# Pirxboard.net
KiCad netlist of a schematic drawn in EAGLE
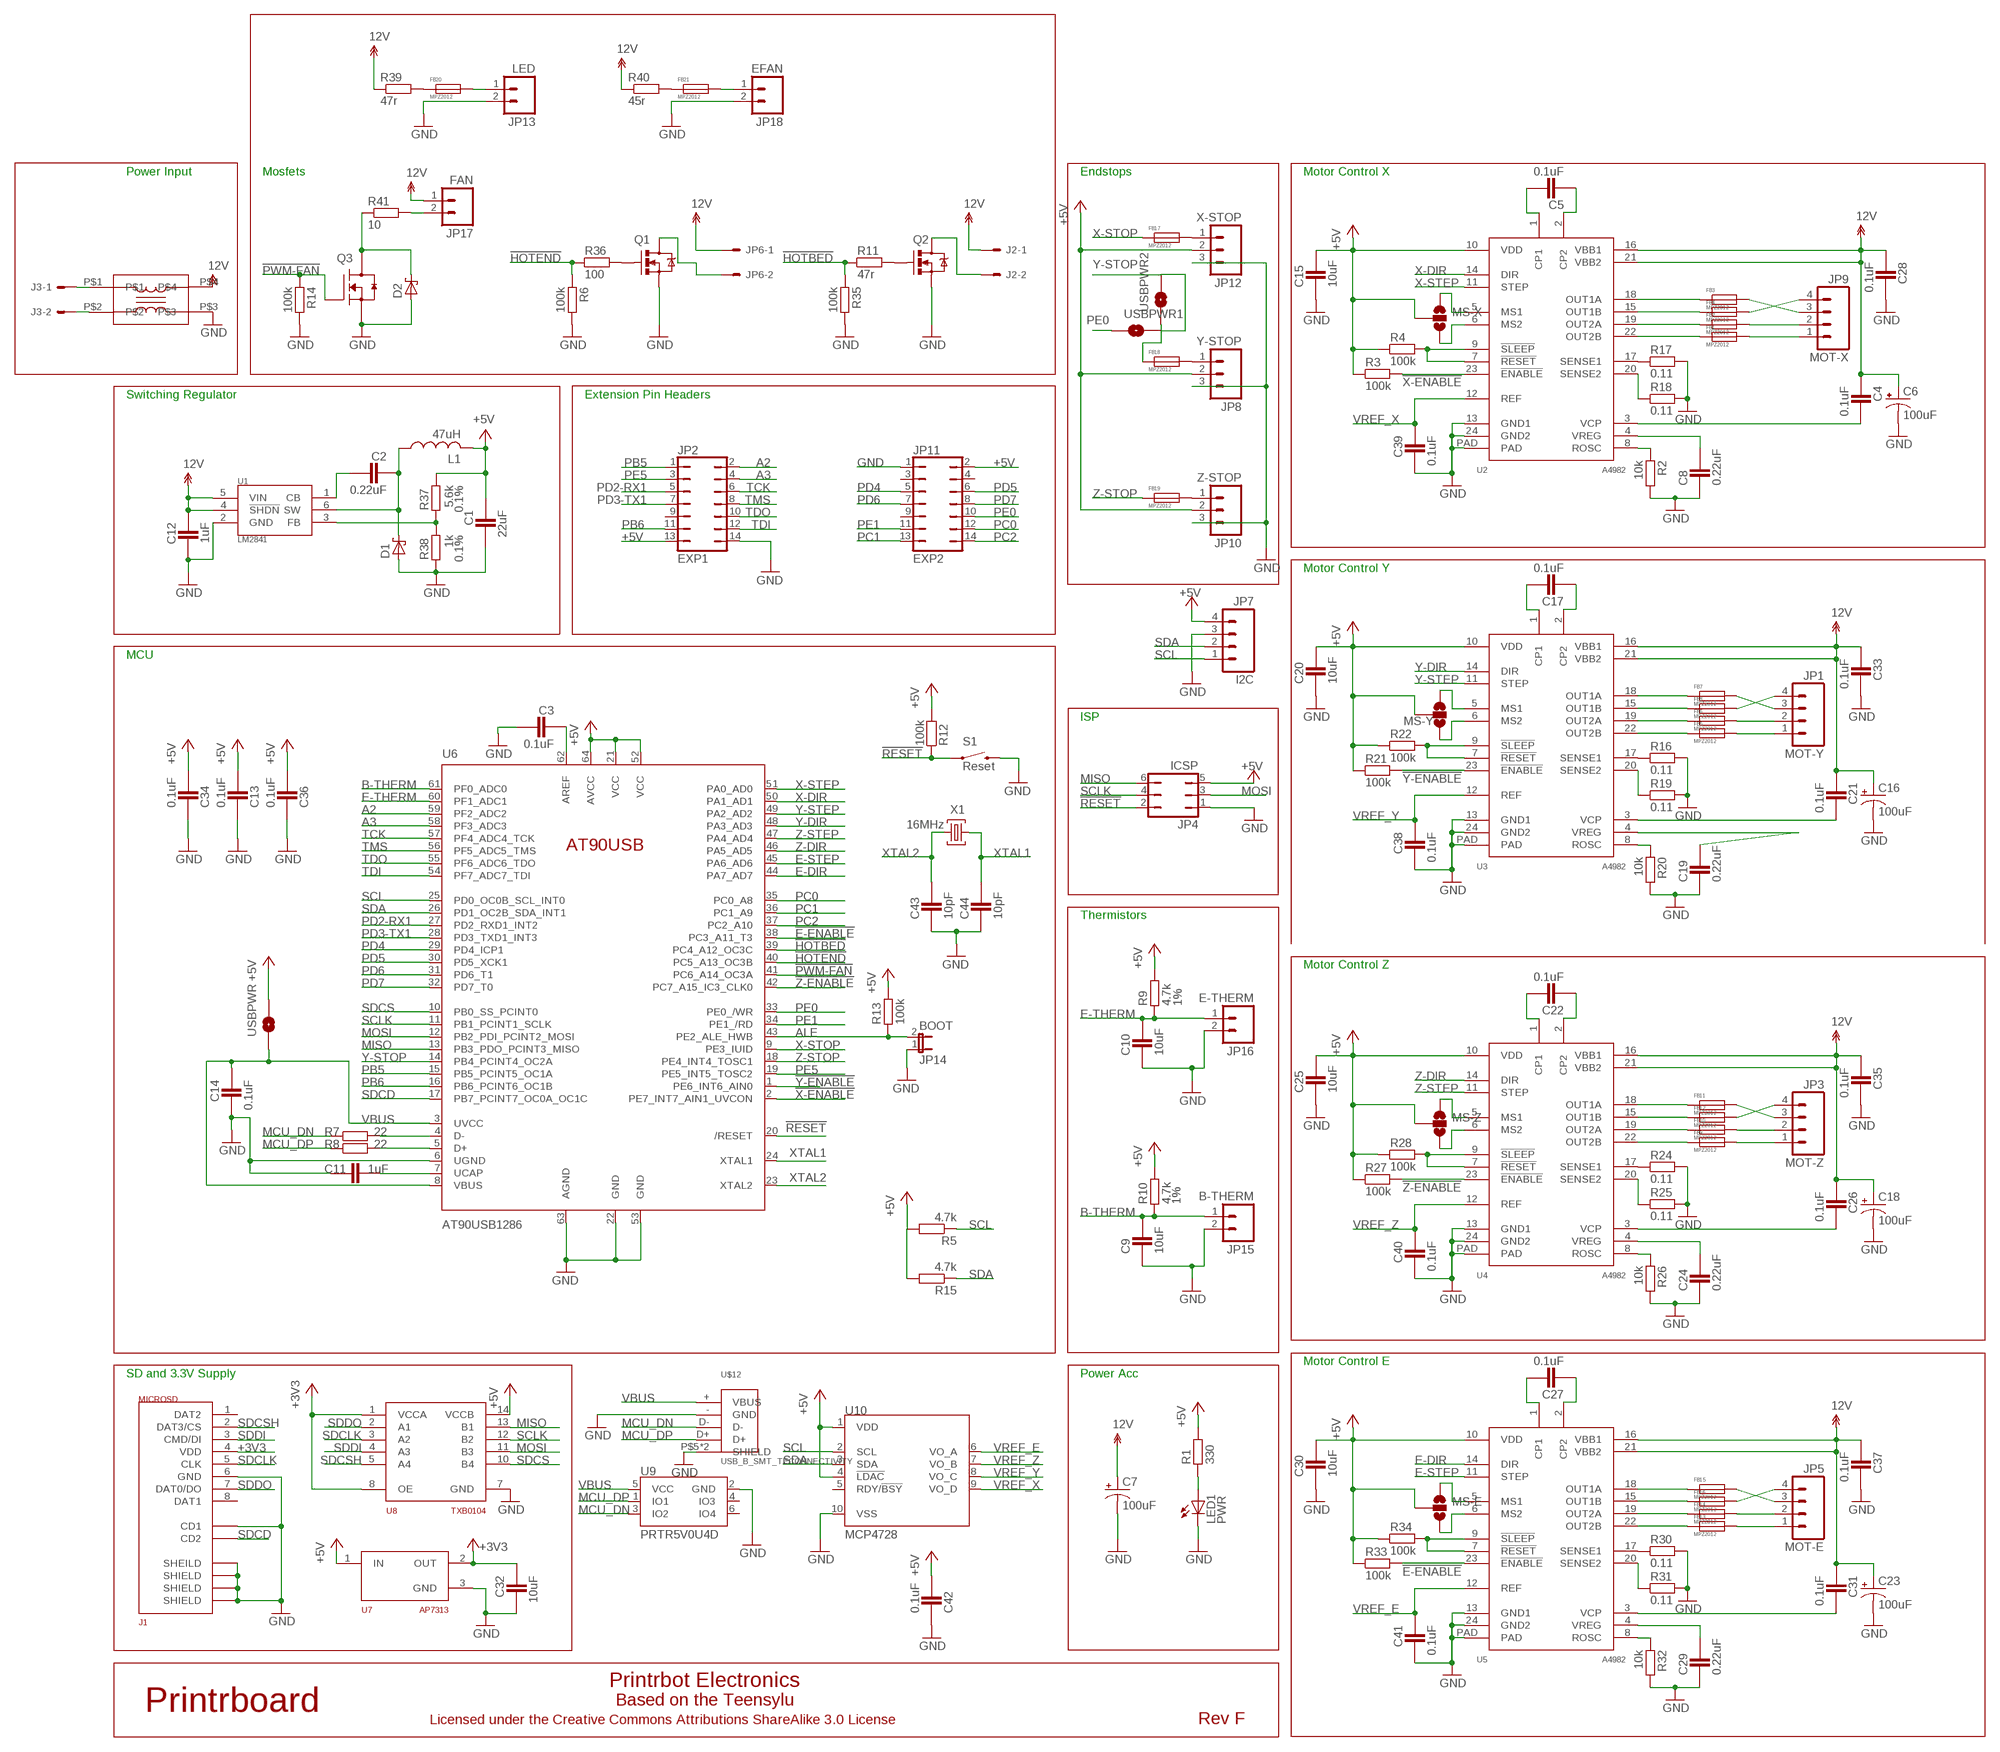
[diagram p0: schematic, sheet 1]

(export (version "E")
  (design (tool "Eeschema 10.0.6"))
  (components
    (comp (ref "C1")
      (value "22uF")
      (footprint "eagle-import:CAPC2012X145AN")
      (libsource (lib "eagle-import") (part "CAPACITOR_0805"))
    )
    (comp (ref "C2")
      (value "0.22uF")
      (footprint "eagle-import:CAPC2012X145AN")
      (libsource (lib "eagle-import") (part "CAPACITOR_0805"))
    )
    (comp (ref "C3")
      (value "0.1uF")
      (footprint "eagle-import:CAPC2012X145AN")
      (libsource (lib "eagle-import") (part "CAPACITOR_0805"))
    )
    (comp (ref "C4")
      (value "0.1uF")
      (footprint "eagle-import:CAPC2012X145AN")
      (libsource (lib "eagle-import") (part "CAPACITOR_0805"))
    )
    (comp (ref "C5")
      (value "0.1uF")
      (footprint "eagle-import:CAPC2012X145AN")
      (libsource (lib "eagle-import") (part "CAPACITOR_0805"))
    )
    (comp (ref "C6")
      (value "100uF")
      (footprint "eagle-import:PANASONIC_D")
      (libsource (lib "eagle-import") (part "CPOL-USD"))
    )
    (comp (ref "C7")
      (value "100uF")
      (footprint "eagle-import:PANASONIC_D")
      (libsource (lib "eagle-import") (part "CPOL-USD"))
    )
    (comp (ref "C8")
      (value "0.22uF")
      (footprint "eagle-import:CAPC2012X145AN")
      (libsource (lib "eagle-import") (part "CAPACITOR_0805"))
    )
    (comp (ref "C9")
      (value "10uF")
      (footprint "eagle-import:CAPC2012X145AN")
      (libsource (lib "eagle-import") (part "CAPACITOR_0805"))
    )
    (comp (ref "C10")
      (value "10uF")
      (footprint "eagle-import:CAPC2012X145AN")
      (libsource (lib "eagle-import") (part "CAPACITOR_0805"))
    )
    (comp (ref "C11")
      (value "1uF")
      (footprint "eagle-import:CAPC2012X145AN")
      (libsource (lib "eagle-import") (part "CAPACITOR_0805"))
    )
    (comp (ref "C12")
      (value "1uF")
      (footprint "eagle-import:CAPC2012X145AN")
      (libsource (lib "eagle-import") (part "CAPACITOR_0805"))
    )
    (comp (ref "C13")
      (value "0.1uF")
      (footprint "eagle-import:CAPC2012X145AN")
      (libsource (lib "eagle-import") (part "CAPACITOR_0805"))
    )
    (comp (ref "C14")
      (value "0.1uF")
      (footprint "eagle-import:CAPC2012X145AN")
      (libsource (lib "eagle-import") (part "CAPACITOR_0805"))
    )
    (comp (ref "C15")
      (value "10uF")
      (footprint "eagle-import:CAPC2012X145AN")
      (libsource (lib "eagle-import") (part "CAPACITOR_0805"))
    )
    (comp (ref "C16")
      (value "100uF")
      (footprint "eagle-import:PANASONIC_D")
      (libsource (lib "eagle-import") (part "CPOL-USD"))
    )
    (comp (ref "C17")
      (value "0.1uF")
      (footprint "eagle-import:CAPC2012X145AN")
      (libsource (lib "eagle-import") (part "CAPACITOR_0805"))
    )
    (comp (ref "C18")
      (value "100uF")
      (footprint "eagle-import:PANASONIC_D")
      (libsource (lib "eagle-import") (part "CPOL-USD"))
    )
    (comp (ref "C19")
      (value "0.22uF")
      (footprint "eagle-import:CAPC2012X145AN")
      (libsource (lib "eagle-import") (part "CAPACITOR_0805"))
    )
    (comp (ref "C20")
      (value "10uF")
      (footprint "eagle-import:CAPC2012X145AN")
      (libsource (lib "eagle-import") (part "CAPACITOR_0805"))
    )
    (comp (ref "C21")
      (value "0.1uF")
      (footprint "eagle-import:CAPC2012X145AN")
      (libsource (lib "eagle-import") (part "CAPACITOR_0805"))
    )
    (comp (ref "C22")
      (value "0.1uF")
      (footprint "eagle-import:CAPC2012X145AN")
      (libsource (lib "eagle-import") (part "CAPACITOR_0805"))
    )
    (comp (ref "C23")
      (value "100uF")
      (footprint "eagle-import:PANASONIC_D")
      (libsource (lib "eagle-import") (part "CPOL-USD"))
    )
    (comp (ref "C24")
      (value "0.22uF")
      (footprint "eagle-import:CAPC2012X145AN")
      (libsource (lib "eagle-import") (part "CAPACITOR_0805"))
    )
    (comp (ref "C25")
      (value "10uF")
      (footprint "eagle-import:CAPC2012X145AN")
      (libsource (lib "eagle-import") (part "CAPACITOR_0805"))
    )
    (comp (ref "C26")
      (value "0.1uF")
      (footprint "eagle-import:CAPC2012X145AN")
      (libsource (lib "eagle-import") (part "CAPACITOR_0805"))
    )
    (comp (ref "C27")
      (value "0.1uF")
      (footprint "eagle-import:CAPC2012X145AN")
      (libsource (lib "eagle-import") (part "CAPACITOR_0805"))
    )
    (comp (ref "C28")
      (value "0.1uF")
      (footprint "eagle-import:CAPC2012X145AN")
      (libsource (lib "eagle-import") (part "CAPACITOR_0805"))
    )
    (comp (ref "C29")
      (value "0.22uF")
      (footprint "eagle-import:CAPC2012X145AN")
      (libsource (lib "eagle-import") (part "CAPACITOR_0805"))
    )
    (comp (ref "C30")
      (value "10uF")
      (footprint "eagle-import:CAPC2012X145AN")
      (libsource (lib "eagle-import") (part "CAPACITOR_0805"))
    )
    (comp (ref "C31")
      (value "0.1uF")
      (footprint "eagle-import:CAPC2012X145AN")
      (libsource (lib "eagle-import") (part "CAPACITOR_0805"))
    )
    (comp (ref "C32")
      (value "10uF")
      (footprint "eagle-import:CAPC2012X145AN")
      (libsource (lib "eagle-import") (part "CAPACITOR_0805"))
    )
    (comp (ref "C33")
      (value "0.1uF")
      (footprint "eagle-import:CAPC2012X145AN")
      (libsource (lib "eagle-import") (part "CAPACITOR_0805"))
    )
    (comp (ref "C34")
      (value "0.1uF")
      (footprint "eagle-import:CAPC2012X145AN")
      (libsource (lib "eagle-import") (part "CAPACITOR_0805"))
    )
    (comp (ref "C35")
      (value "0.1uF")
      (footprint "eagle-import:CAPC2012X145AN")
      (libsource (lib "eagle-import") (part "CAPACITOR_0805"))
    )
    (comp (ref "C36")
      (value "0.1uF")
      (footprint "eagle-import:CAPC2012X145AN")
      (libsource (lib "eagle-import") (part "CAPACITOR_0805"))
    )
    (comp (ref "C37")
      (value "0.1uF")
      (footprint "eagle-import:CAPC2012X145AN")
      (libsource (lib "eagle-import") (part "CAPACITOR_0805"))
    )
    (comp (ref "C38")
      (value "0.1uF")
      (footprint "eagle-import:CAPC2012X145AN")
      (libsource (lib "eagle-import") (part "CAPACITOR_0805"))
    )
    (comp (ref "C39")
      (value "0.1uF")
      (footprint "eagle-import:CAPC2012X145AN")
      (libsource (lib "eagle-import") (part "CAPACITOR_0805"))
    )
    (comp (ref "C40")
      (value "0.1uF")
      (footprint "eagle-import:CAPC2012X145AN")
      (libsource (lib "eagle-import") (part "CAPACITOR_0805"))
    )
    (comp (ref "C41")
      (value "0.1uF")
      (footprint "eagle-import:CAPC2012X145AN")
      (libsource (lib "eagle-import") (part "CAPACITOR_0805"))
    )
    (comp (ref "C42")
      (value "0.1uF")
      (footprint "eagle-import:CAPC2012X145AN")
      (libsource (lib "eagle-import") (part "CAPACITOR_0805"))
    )
    (comp (ref "C43")
      (value "10pF")
      (footprint "eagle-import:CAPC2012X145AN")
      (libsource (lib "eagle-import") (part "CAPACITOR_0805"))
    )
    (comp (ref "C44")
      (value "10pF")
      (footprint "eagle-import:CAPC2012X145AN")
      (libsource (lib "eagle-import") (part "CAPACITOR_0805"))
    )
    (comp (ref "D1")
      (value "SCH-DIODESMA")
      (footprint "eagle-import:SMA")
      (libsource (lib "eagle-import") (part "SCH-DIODESMA"))
    )
    (comp (ref "D2")
      (value "SCH-DIODESMA")
      (footprint "eagle-import:SMA")
      (libsource (lib "eagle-import") (part "SCH-DIODESMA"))
    )
    (comp (ref "FB1")
      (value "MPZ2012")
      (footprint "eagle-import:FB2012")
      (libsource (lib "eagle-import") (part "MPZ2012"))
    )
    (comp (ref "FB2")
      (value "MPZ2012")
      (footprint "eagle-import:FB2012")
      (libsource (lib "eagle-import") (part "MPZ2012"))
    )
    (comp (ref "FB3")
      (value "MPZ2012")
      (footprint "eagle-import:FB2012")
      (libsource (lib "eagle-import") (part "MPZ2012"))
    )
    (comp (ref "FB4")
      (value "MPZ2012")
      (footprint "eagle-import:FB2012")
      (libsource (lib "eagle-import") (part "MPZ2012"))
    )
    (comp (ref "FB5")
      (value "MPZ2012")
      (footprint "eagle-import:FB2012")
      (libsource (lib "eagle-import") (part "MPZ2012"))
    )
    (comp (ref "FB6")
      (value "MPZ2012")
      (footprint "eagle-import:FB2012")
      (libsource (lib "eagle-import") (part "MPZ2012"))
    )
    (comp (ref "FB7")
      (value "MPZ2012")
      (footprint "eagle-import:FB2012")
      (libsource (lib "eagle-import") (part "MPZ2012"))
    )
    (comp (ref "FB8")
      (value "MPZ2012")
      (footprint "eagle-import:FB2012")
      (libsource (lib "eagle-import") (part "MPZ2012"))
    )
    (comp (ref "FB9")
      (value "MPZ2012")
      (footprint "eagle-import:FB2012")
      (libsource (lib "eagle-import") (part "MPZ2012"))
    )
    (comp (ref "FB10")
      (value "MPZ2012")
      (footprint "eagle-import:FB2012")
      (libsource (lib "eagle-import") (part "MPZ2012"))
    )
    (comp (ref "FB11")
      (value "MPZ2012")
      (footprint "eagle-import:FB2012")
      (libsource (lib "eagle-import") (part "MPZ2012"))
    )
    (comp (ref "FB12")
      (value "MPZ2012")
      (footprint "eagle-import:FB2012")
      (libsource (lib "eagle-import") (part "MPZ2012"))
    )
    (comp (ref "FB13")
      (value "MPZ2012")
      (footprint "eagle-import:FB2012")
      (libsource (lib "eagle-import") (part "MPZ2012"))
    )
    (comp (ref "FB14")
      (value "MPZ2012")
      (footprint "eagle-import:FB2012")
      (libsource (lib "eagle-import") (part "MPZ2012"))
    )
    (comp (ref "FB15")
      (value "MPZ2012")
      (footprint "eagle-import:FB2012")
      (libsource (lib "eagle-import") (part "MPZ2012"))
    )
    (comp (ref "FB16")
      (value "MPZ2012")
      (footprint "eagle-import:FB2012")
      (libsource (lib "eagle-import") (part "MPZ2012"))
    )
    (comp (ref "FB17")
      (value "MPZ2012")
      (footprint "eagle-import:FB2012")
      (libsource (lib "eagle-import") (part "MPZ2012"))
    )
    (comp (ref "FB18")
      (value "MPZ2012")
      (footprint "eagle-import:FB2012")
      (libsource (lib "eagle-import") (part "MPZ2012"))
    )
    (comp (ref "FB19")
      (value "MPZ2012")
      (footprint "eagle-import:FB2012")
      (libsource (lib "eagle-import") (part "MPZ2012"))
    )
    (comp (ref "FB20")
      (value "MPZ2012")
      (footprint "eagle-import:FB2012")
      (libsource (lib "eagle-import") (part "MPZ2012"))
    )
    (comp (ref "FB21")
      (value "MPZ2012")
      (footprint "eagle-import:FB2012")
      (libsource (lib "eagle-import") (part "MPZ2012"))
    )
    (comp (ref "J1")
      (value "MICROSD")
      (footprint "eagle-import:AMPHENOL-MICROSD")
      (libsource (lib "eagle-import") (part "MICROSD"))
    )
    (comp (ref "J2")
      (value "PHOENIX-2POS-5MM-SCREW")
      (footprint "eagle-import:PHOENIX-5MM-2POS")
      (libsource (lib "eagle-import") (part "PHOENIX-2POS-5MM-SCREW"))
    )
    (comp (ref "J3")
      (value "PHOENIX-2POS-5MM-SCREW")
      (footprint "eagle-import:PHOENIX-5MM-2POS")
      (libsource (lib "eagle-import") (part "PHOENIX-2POS-5MM-SCREW"))
    )
    (comp (ref "JP1")
      (value "MOT-Y")
      (footprint "eagle-import:MOLEX-1X4")
      (libsource (lib "eagle-import") (part "M04POLAR"))
    )
    (comp (ref "JP2")
      (value "EXP1")
      (footprint "eagle-import:JP7Q")
      (libsource (lib "eagle-import") (part "JP7Q"))
    )
    (comp (ref "JP3")
      (value "MOT-Z")
      (footprint "eagle-import:MOLEX-1X4")
      (libsource (lib "eagle-import") (part "M04POLAR"))
    )
    (comp (ref "JP4")
      (value "ICSP")
      (footprint "eagle-import:JP3Q")
      (libsource (lib "eagle-import") (part "JP3Q"))
    )
    (comp (ref "JP5")
      (value "MOT-E")
      (footprint "eagle-import:MOLEX-1X4")
      (libsource (lib "eagle-import") (part "M04POLAR"))
    )
    (comp (ref "JP6")
      (value "PHOENIX-2POS-5MM-SCREW")
      (footprint "eagle-import:PHOENIX-5MM-2POS")
      (libsource (lib "eagle-import") (part "PHOENIX-2POS-5MM-SCREW"))
    )
    (comp (ref "JP7")
      (value "I2C")
      (footprint "eagle-import:MOLEX-1X4")
      (libsource (lib "eagle-import") (part "M04POLAR"))
    )
    (comp (ref "JP8")
      (value "Y-STOP")
      (footprint "eagle-import:MOLEX-1X3")
      (libsource (lib "eagle-import") (part "M03POLAR"))
    )
    (comp (ref "JP9")
      (value "MOT-X")
      (footprint "eagle-import:MOLEX-1X4")
      (libsource (lib "eagle-import") (part "M04POLAR"))
    )
    (comp (ref "JP10")
      (value "Z-STOP")
      (footprint "eagle-import:MOLEX-1X3")
      (libsource (lib "eagle-import") (part "M03POLAR"))
    )
    (comp (ref "JP11")
      (value "EXP2")
      (footprint "eagle-import:JP7Q")
      (libsource (lib "eagle-import") (part "JP7Q"))
    )
    (comp (ref "JP12")
      (value "X-STOP")
      (footprint "eagle-import:MOLEX-1X3")
      (libsource (lib "eagle-import") (part "M03POLAR"))
    )
    (comp (ref "JP13")
      (value "LED")
      (footprint "eagle-import:1X02")
      (libsource (lib "eagle-import") (part "M02PTH"))
    )
    (comp (ref "JP14")
      (value "BOOT")
      (footprint "eagle-import:1X02")
      (libsource (lib "eagle-import") (part "JUMPER-2PTH"))
    )
    (comp (ref "JP15")
      (value "B-THERM")
      (footprint "eagle-import:1X02")
      (libsource (lib "eagle-import") (part "M02PTH"))
    )
    (comp (ref "JP16")
      (value "E-THERM")
      (footprint "eagle-import:1X02")
      (libsource (lib "eagle-import") (part "M02PTH"))
    )
    (comp (ref "JP17")
      (value "FAN")
      (footprint "eagle-import:1X02")
      (libsource (lib "eagle-import") (part "M02PTH"))
    )
    (comp (ref "JP18")
      (value "EFAN")
      (footprint "eagle-import:1X02")
      (libsource (lib "eagle-import") (part "M02PTH"))
    )
    (comp (ref "L1")
      (value "47uH")
      (footprint "eagle-import:SDR1006")
      (libsource (lib "eagle-import") (part "L-US"))
    )
    (comp (ref "LED1")
      (value "PWR")
      (footprint "eagle-import:CHIP-LED0805")
      (libsource (lib "eagle-import") (part "LEDCHIP-LED0805"))
    )
    (comp (ref "MS-E")
      (value "SOLDERJUMPER_2WAYCONNECTED")
      (footprint "eagle-import:SJ_3_CONNECTED")
      (libsource (lib "eagle-import") (part "SOLDERJUMPER_2WAYCONNECTED"))
    )
    (comp (ref "MS-X")
      (value "SOLDERJUMPER_2WAYCONNECTED")
      (footprint "eagle-import:SJ_3_CONNECTED")
      (libsource (lib "eagle-import") (part "SOLDERJUMPER_2WAYCONNECTED"))
    )
    (comp (ref "MS-Y")
      (value "SOLDERJUMPER_2WAYCONNECTED")
      (footprint "eagle-import:SJ_3_CONNECTED")
      (libsource (lib "eagle-import") (part "SOLDERJUMPER_2WAYCONNECTED"))
    )
    (comp (ref "MS-Z")
      (value "SOLDERJUMPER_2WAYCONNECTED")
      (footprint "eagle-import:SJ_3_CONNECTED")
      (libsource (lib "eagle-import") (part "SOLDERJUMPER_2WAYCONNECTED"))
    )
    (comp (ref "Q1")
      (value "RFP30N06LE")
      (footprint "eagle-import:TO220V")
      (libsource (lib "eagle-import") (part "MOSFET-NCHANNELPTH2"))
    )
    (comp (ref "Q2")
      (value "RFP30N06LE")
      (footprint "eagle-import:TO220V")
      (libsource (lib "eagle-import") (part "MOSFET-NCHANNELPTH2"))
    )
    (comp (ref "Q3")
      (value "RFP30N06LE")
      (footprint "eagle-import:SOT95P280X135-3N")
      (libsource (lib "eagle-import") (part "MOSFET-NCH_SOT-23"))
    )
    (comp (ref "R1")
      (value "330")
      (footprint "eagle-import:RESC2012X70N")
      (libsource (lib "eagle-import") (part "RESISTOR_0805"))
    )
    (comp (ref "R2")
      (value "10k")
      (footprint "eagle-import:RESC2012X70N")
      (libsource (lib "eagle-import") (part "RESISTOR_0805"))
    )
    (comp (ref "R3")
      (value "100k")
      (footprint "eagle-import:RESC2012X70N")
      (libsource (lib "eagle-import") (part "RESISTOR_0805"))
    )
    (comp (ref "R4")
      (value "100k")
      (footprint "eagle-import:RESC2012X70N")
      (libsource (lib "eagle-import") (part "RESISTOR_0805"))
    )
    (comp (ref "R5")
      (value "4.7k")
      (footprint "eagle-import:RESC2012X70N")
      (libsource (lib "eagle-import") (part "RESISTOR_0805"))
    )
    (comp (ref "R6")
      (value "100k")
      (footprint "eagle-import:RESC2012X70N")
      (libsource (lib "eagle-import") (part "RESISTOR_0805"))
    )
    (comp (ref "R7")
      (value "22")
      (footprint "eagle-import:RESC2012X70N")
      (libsource (lib "eagle-import") (part "RESISTOR_0805"))
    )
    (comp (ref "R8")
      (value "22")
      (footprint "eagle-import:RESC2012X70N")
      (libsource (lib "eagle-import") (part "RESISTOR_0805"))
    )
    (comp (ref "R9")
      (value "4.7k")
      (footprint "eagle-import:RESC2012X70N")
      (fields (field (name "TOLERANCE") "1%"))
      (libsource (lib "eagle-import") (part "RESISTOR_0805"))
    )
    (comp (ref "R10")
      (value "4.7k")
      (footprint "eagle-import:RESC2012X70N")
      (fields (field (name "TOLERANCE") "1%"))
      (libsource (lib "eagle-import") (part "RESISTOR_0805"))
    )
    (comp (ref "R11")
      (value "47r")
      (footprint "eagle-import:RESC2012X70N")
      (libsource (lib "eagle-import") (part "RESISTOR_0805"))
    )
    (comp (ref "R12")
      (value "100k")
      (footprint "eagle-import:RESC2012X70N")
      (libsource (lib "eagle-import") (part "RESISTOR_0805"))
    )
    (comp (ref "R13")
      (value "100k")
      (footprint "eagle-import:RESC2012X70N")
      (libsource (lib "eagle-import") (part "RESISTOR_0805"))
    )
    (comp (ref "R14")
      (value "100k")
      (footprint "eagle-import:RESC2012X70N")
      (libsource (lib "eagle-import") (part "RESISTOR_0805"))
    )
    (comp (ref "R15")
      (value "4.7k")
      (footprint "eagle-import:RESC2012X70N")
      (libsource (lib "eagle-import") (part "RESISTOR_0805"))
    )
    (comp (ref "R16")
      (value "0.11")
      (footprint "eagle-import:RESC2012X70N")
      (libsource (lib "eagle-import") (part "RESISTOR_0805"))
    )
    (comp (ref "R17")
      (value "0.11")
      (footprint "eagle-import:RESC2012X70N")
      (libsource (lib "eagle-import") (part "RESISTOR_0805"))
    )
    (comp (ref "R18")
      (value "0.11")
      (footprint "eagle-import:RESC2012X70N")
      (libsource (lib "eagle-import") (part "RESISTOR_0805"))
    )
    (comp (ref "R19")
      (value "0.11")
      (footprint "eagle-import:RESC2012X70N")
      (libsource (lib "eagle-import") (part "RESISTOR_0805"))
    )
    (comp (ref "R20")
      (value "10k")
      (footprint "eagle-import:RESC2012X70N")
      (libsource (lib "eagle-import") (part "RESISTOR_0805"))
    )
    (comp (ref "R21")
      (value "100k")
      (footprint "eagle-import:RESC2012X70N")
      (libsource (lib "eagle-import") (part "RESISTOR_0805"))
    )
    (comp (ref "R22")
      (value "100k")
      (footprint "eagle-import:RESC2012X70N")
      (libsource (lib "eagle-import") (part "RESISTOR_0805"))
    )
    (comp (ref "R24")
      (value "0.11")
      (footprint "eagle-import:RESC2012X70N")
      (libsource (lib "eagle-import") (part "RESISTOR_0805"))
    )
    (comp (ref "R25")
      (value "0.11")
      (footprint "eagle-import:RESC2012X70N")
      (libsource (lib "eagle-import") (part "RESISTOR_0805"))
    )
    (comp (ref "R26")
      (value "10k")
      (footprint "eagle-import:RESC2012X70N")
      (libsource (lib "eagle-import") (part "RESISTOR_0805"))
    )
    (comp (ref "R27")
      (value "100k")
      (footprint "eagle-import:RESC2012X70N")
      (libsource (lib "eagle-import") (part "RESISTOR_0805"))
    )
    (comp (ref "R28")
      (value "100k")
      (footprint "eagle-import:RESC2012X70N")
      (libsource (lib "eagle-import") (part "RESISTOR_0805"))
    )
    (comp (ref "R30")
      (value "0.11")
      (footprint "eagle-import:RESC2012X70N")
      (libsource (lib "eagle-import") (part "RESISTOR_0805"))
    )
    (comp (ref "R31")
      (value "0.11")
      (footprint "eagle-import:RESC2012X70N")
      (libsource (lib "eagle-import") (part "RESISTOR_0805"))
    )
    (comp (ref "R32")
      (value "10k")
      (footprint "eagle-import:RESC2012X70N")
      (libsource (lib "eagle-import") (part "RESISTOR_0805"))
    )
    (comp (ref "R33")
      (value "100k")
      (footprint "eagle-import:RESC2012X70N")
      (libsource (lib "eagle-import") (part "RESISTOR_0805"))
    )
    (comp (ref "R34")
      (value "100k")
      (footprint "eagle-import:RESC2012X70N")
      (libsource (lib "eagle-import") (part "RESISTOR_0805"))
    )
    (comp (ref "R35")
      (value "100k")
      (footprint "eagle-import:RESC2012X70N")
      (libsource (lib "eagle-import") (part "RESISTOR_0805"))
    )
    (comp (ref "R36")
      (value "100")
      (footprint "eagle-import:RESC2012X70N")
      (libsource (lib "eagle-import") (part "RESISTOR_0805"))
    )
    (comp (ref "R37")
      (value "5.6k")
      (footprint "eagle-import:RESC2012X70N")
      (fields (field (name "TOLERANCE") "0.1%"))
      (libsource (lib "eagle-import") (part "RESISTOR_0805"))
    )
    (comp (ref "R38")
      (value "1k")
      (footprint "eagle-import:RESC2012X70N")
      (fields (field (name "TOLERANCE") "0.1%"))
      (libsource (lib "eagle-import") (part "RESISTOR_0805"))
    )
    (comp (ref "R39")
      (value "47r")
      (footprint "eagle-import:R2512")
      (libsource (lib "eagle-import") (part "R-EU_R2512"))
    )
    (comp (ref "R40")
      (value "45r")
      (footprint "eagle-import:R2512")
      (libsource (lib "eagle-import") (part "R-EU_R2512"))
    )
    (comp (ref "R41")
      (value "10")
      (footprint "eagle-import:R2512")
      (libsource (lib "eagle-import") (part "R-EU_R2512"))
    )
    (comp (ref "S1")
      (value "Reset")
      (footprint "eagle-import:TACTILE_SWITCH_TALL")
      (libsource (lib "eagle-import") (part "SWITCH-MOMENTARY-2"))
    )
    (comp (ref "U$8")
      (value "ACM1513-551-2PLACM1513")
      (footprint "eagle-import:ACM1513")
      (libsource (lib "eagle-import") (part "ACM1513-551-2PLACM1513"))
    )
    (comp (ref "U$12")
      (value "USB_B_SMT_TECONNECTIVITY")
      (footprint "eagle-import:TECONECTIVITYUSBBSMT")
      (libsource (lib "eagle-import") (part "USB_B_SMT_TECONNECTIVITY"))
    )
    (comp (ref "U1")
      (value "LM2841")
      (footprint "eagle-import:TSOT6")
      (libsource (lib "eagle-import") (part "LM2841"))
    )
    (comp (ref "U2")
      (value "A4982")
      (footprint "eagle-import:TSSOP-24")
      (libsource (lib "eagle-import") (part "A4982"))
    )
    (comp (ref "U3")
      (value "A4982")
      (footprint "eagle-import:TSSOP-24")
      (libsource (lib "eagle-import") (part "A4982"))
    )
    (comp (ref "U4")
      (value "A4982")
      (footprint "eagle-import:TSSOP-24")
      (libsource (lib "eagle-import") (part "A4982"))
    )
    (comp (ref "U5")
      (value "A4982")
      (footprint "eagle-import:TSSOP-24")
      (libsource (lib "eagle-import") (part "A4982"))
    )
    (comp (ref "U6")
      (value "AT90USB1286")
      (footprint "eagle-import:TQFP64-2")
      (libsource (lib "eagle-import") (part "AT90USB"))
    )
    (comp (ref "U7")
      (value "AP7313")
      (footprint "eagle-import:SOT23C")
      (libsource (lib "eagle-import") (part "AP7313"))
    )
    (comp (ref "U8")
      (value "TXB0104")
      (footprint "eagle-import:TSSOP14")
      (libsource (lib "eagle-import") (part "TXB0104"))
    )
    (comp (ref "U9")
      (value "PRTR5V0U4D")
      (footprint "eagle-import:SOT23-6")
      (libsource (lib "eagle-import") (part "PRTR5V0U4D"))
    )
    (comp (ref "U10")
      (value "MCP4728")
      (footprint "eagle-import:MSOP10")
      (libsource (lib "eagle-import") (part "MCP4728"))
    )
    (comp (ref "USBPWR")
      (value "SOLDERJUMPERNO")
      (footprint "eagle-import:SJ_2S-NO")
      (libsource (lib "eagle-import") (part "SOLDERJUMPERNO"))
    )
    (comp (ref "USBPWR1")
      (value "SOLDERJUMPERNO")
      (footprint "eagle-import:SJ_2S-NO")
      (libsource (lib "eagle-import") (part "SOLDERJUMPERNO"))
    )
    (comp (ref "USBPWR2")
      (value "SOLDERJUMPERNO")
      (footprint "eagle-import:SJ_2S-NO")
      (libsource (lib "eagle-import") (part "SOLDERJUMPERNO"))
    )
    (comp (ref "X1")
      (value "16MHz")
      (footprint "eagle-import:NDK-XTAL")
      (libsource (lib "eagle-import") (part "XTAL"))
    )
  )
  (nets
    (net (code "1") (name "+3V3") (class "Default")
      (node (ref "C32") (pin "1") (pinfunction "1_1") (pintype "passive"))
      (node (ref "J1") (pin "4") (pinfunction "VDD_4") (pintype "power_in"))
      (node (ref "U7") (pin "2") (pinfunction "OUT_2") (pintype "power_in"))
      (node (ref "U8") (pin "1") (pinfunction "VCCA_1") (pintype "power_in"))
      (node (ref "U8") (pin "8") (pinfunction "OE_8") (pintype "input"))
    )
    (net (code "2") (name "+5V") (class "Default")
      (node (ref "C1") (pin "1") (pinfunction "1_1") (pintype "passive"))
      (node (ref "C13") (pin "2") (pinfunction "2_2") (pintype "passive"))
      (node (ref "C15") (pin "2") (pinfunction "2_2") (pintype "passive"))
      (node (ref "C20") (pin "2") (pinfunction "2_2") (pintype "passive"))
      (node (ref "C25") (pin "2") (pinfunction "2_2") (pintype "passive"))
      (node (ref "C30") (pin "2") (pinfunction "2_2") (pintype "passive"))
      (node (ref "C34") (pin "2") (pinfunction "2_2") (pintype "passive"))
      (node (ref "C36") (pin "2") (pinfunction "2_2") (pintype "passive"))
      (node (ref "C42") (pin "2") (pinfunction "2_2") (pintype "passive"))
      (node (ref "JP10") (pin "2") (pinfunction "2_2") (pintype "passive"))
      (node (ref "JP11") (pin "2") (pinfunction "2_2") (pintype "passive"))
      (node (ref "JP12") (pin "2") (pinfunction "2_2") (pintype "passive"))
      (node (ref "JP2") (pin "13") (pinfunction "13_13") (pintype "passive"))
      (node (ref "JP4") (pin "5") (pinfunction "5_5") (pintype "passive"))
      (node (ref "JP7") (pin "4") (pinfunction "4_4") (pintype "passive"))
      (node (ref "JP8") (pin "2") (pinfunction "2_2") (pintype "passive"))
      (node (ref "L1") (pin "P$2") (pinfunction "2_P$2") (pintype "passive"))
      (node (ref "MS-E") (pin "2") (pinfunction "2_2") (pintype "passive"))
      (node (ref "MS-X") (pin "2") (pinfunction "2_2") (pintype "passive"))
      (node (ref "MS-Y") (pin "2") (pinfunction "2_2") (pintype "passive"))
      (node (ref "MS-Z") (pin "2") (pinfunction "2_2") (pintype "passive"))
      (node (ref "R1") (pin "2") (pinfunction "2_2") (pintype "passive"))
      (node (ref "R10") (pin "2") (pinfunction "2_2") (pintype "passive"))
      (node (ref "R12") (pin "2") (pinfunction "2_2") (pintype "passive"))
      (node (ref "R13") (pin "2") (pinfunction "2_2") (pintype "passive"))
      (node (ref "R15") (pin "2") (pinfunction "2_2") (pintype "passive"))
      (node (ref "R21") (pin "1") (pinfunction "1_1") (pintype "passive"))
      (node (ref "R22") (pin "1") (pinfunction "1_1") (pintype "passive"))
      (node (ref "R27") (pin "1") (pinfunction "1_1") (pintype "passive"))
      (node (ref "R28") (pin "1") (pinfunction "1_1") (pintype "passive"))
      (node (ref "R3") (pin "1") (pinfunction "1_1") (pintype "passive"))
      (node (ref "R33") (pin "1") (pinfunction "1_1") (pintype "passive"))
      (node (ref "R34") (pin "1") (pinfunction "1_1") (pintype "passive"))
      (node (ref "R37") (pin "1") (pinfunction "1_1") (pintype "passive"))
      (node (ref "R4") (pin "1") (pinfunction "1_1") (pintype "passive"))
      (node (ref "R5") (pin "2") (pinfunction "2_2") (pintype "passive"))
      (node (ref "R9") (pin "2") (pinfunction "2_2") (pintype "passive"))
      (node (ref "U10") (pin "1") (pinfunction "VDD_1") (pintype "power_in"))
      (node (ref "U10") (pin "4") (pinfunction "~{LDAC}_4") (pintype "input"))
      (node (ref "U2") (pin "10") (pinfunction "VDD_10") (pintype "power_in"))
      (node (ref "U3") (pin "10") (pinfunction "VDD_10") (pintype "power_in"))
      (node (ref "U4") (pin "10") (pinfunction "VDD_10") (pintype "power_in"))
      (node (ref "U5") (pin "10") (pinfunction "VDD_10") (pintype "power_in"))
      (node (ref "U6") (pin "21") (pinfunction "VCC_21") (pintype "power_in"))
      (node (ref "U6") (pin "52") (pinfunction "VCC_52") (pintype "power_in"))
      (node (ref "U6") (pin "64") (pinfunction "AVCC_64") (pintype "power_in"))
      (node (ref "U7") (pin "1") (pinfunction "IN_1") (pintype "power_in"))
      (node (ref "U8") (pin "14") (pinfunction "VCCB_14") (pintype "power_in"))
      (node (ref "USBPWR") (pin "2") (pinfunction "2_2") (pintype "passive"))
    )
    (net (code "3") (name "/A2") (class "Default")
      (node (ref "JP2") (pin "2") (pinfunction "2_2") (pintype "passive"))
      (node (ref "U6") (pin "59") (pinfunction "PF2_ADC2_59") (pintype "bidirectional"))
    )
    (net (code "4") (name "/A3") (class "Default")
      (node (ref "JP2") (pin "4") (pinfunction "4_4") (pintype "passive"))
      (node (ref "U6") (pin "58") (pinfunction "PF3_ADC3_58") (pintype "bidirectional"))
    )
    (net (code "5") (name "/ALE") (class "Default")
      (node (ref "JP14") (pin "2") (pinfunction "2_2") (pintype "passive"))
      (node (ref "R13") (pin "1") (pinfunction "1_1") (pintype "passive"))
      (node (ref "U6") (pin "43") (pinfunction "PE2_ALE_HWB_43") (pintype "bidirectional"))
    )
    (net (code "6") (name "/B-THERM") (class "Default")
      (node (ref "C9") (pin "2") (pinfunction "2_2") (pintype "passive"))
      (node (ref "JP15") (pin "1") (pinfunction "1_1") (pintype "passive"))
      (node (ref "R10") (pin "1") (pinfunction "1_1") (pintype "passive"))
      (node (ref "U6") (pin "61") (pinfunction "PF0_ADC0_61") (pintype "bidirectional"))
    )
    (net (code "7") (name "/E-DIR") (class "Default")
      (node (ref "U5") (pin "14") (pinfunction "DIR_14") (pintype "input"))
      (node (ref "U6") (pin "44") (pinfunction "PA7_AD7_44") (pintype "bidirectional"))
    )
    (net (code "8") (name "/E-STEP") (class "Default")
      (node (ref "U5") (pin "11") (pinfunction "STEP_11") (pintype "input"))
      (node (ref "U6") (pin "45") (pinfunction "PA6_AD6_45") (pintype "bidirectional"))
    )
    (net (code "9") (name "/E-THERM") (class "Default")
      (node (ref "C10") (pin "2") (pinfunction "2_2") (pintype "passive"))
      (node (ref "JP16") (pin "1") (pinfunction "1_1") (pintype "passive"))
      (node (ref "R9") (pin "1") (pinfunction "1_1") (pintype "passive"))
      (node (ref "U6") (pin "60") (pinfunction "PF1_ADC1_60") (pintype "bidirectional"))
    )
    (net (code "10") (name "/MCU_DN") (class "Default")
      (node (ref "R7") (pin "1") (pinfunction "1_1") (pintype "passive"))
      (node (ref "U$12") (pin "D-") (pinfunction "D-_D-") (pintype "bidirectional"))
      (node (ref "U9") (pin "3") (pinfunction "IO2_3") (pintype "bidirectional"))
    )
    (net (code "11") (name "/MCU_DP") (class "Default")
      (node (ref "R8") (pin "1") (pinfunction "1_1") (pintype "passive"))
      (node (ref "U$12") (pin "D+") (pinfunction "D+_D+") (pintype "bidirectional"))
      (node (ref "U9") (pin "1") (pinfunction "IO1_1") (pintype "bidirectional"))
    )
    (net (code "12") (name "/MISO") (class "Default")
      (node (ref "JP4") (pin "6") (pinfunction "6_6") (pintype "passive"))
      (node (ref "U6") (pin "13") (pinfunction "PB3_PDO_PCINT3_MISO_13") (pintype "bidirectional"))
      (node (ref "U8") (pin "13") (pinfunction "B1_13") (pintype "bidirectional"))
    )
    (net (code "13") (name "/MOSI") (class "Default")
      (node (ref "JP4") (pin "3") (pinfunction "3_3") (pintype "passive"))
      (node (ref "U6") (pin "12") (pinfunction "PB2_PDI_PCINT2_MOSI_12") (pintype "bidirectional"))
      (node (ref "U8") (pin "11") (pinfunction "B3_11") (pintype "bidirectional"))
    )
    (net (code "14") (name "/PB5") (class "Default")
      (node (ref "JP2") (pin "1") (pinfunction "1_1") (pintype "passive"))
      (node (ref "U6") (pin "15") (pinfunction "PB5_PCINT5_OC1A_15") (pintype "bidirectional"))
    )
    (net (code "15") (name "/PB6") (class "Default")
      (node (ref "JP2") (pin "11") (pinfunction "11_11") (pintype "passive"))
      (node (ref "U6") (pin "16") (pinfunction "PB6_PCINT6_OC1B_16") (pintype "bidirectional"))
    )
    (net (code "16") (name "/PC0") (class "Default")
      (node (ref "JP11") (pin "12") (pinfunction "12_12") (pintype "passive"))
      (node (ref "U6") (pin "35") (pinfunction "PC0_A8_35") (pintype "bidirectional"))
    )
    (net (code "17") (name "/PC1") (class "Default")
      (node (ref "JP11") (pin "13") (pinfunction "13_13") (pintype "passive"))
      (node (ref "U6") (pin "36") (pinfunction "PC1_A9_36") (pintype "bidirectional"))
    )
    (net (code "18") (name "/PC2") (class "Default")
      (node (ref "JP11") (pin "14") (pinfunction "14_14") (pintype "passive"))
      (node (ref "U6") (pin "37") (pinfunction "PC2_A10_37") (pintype "bidirectional"))
    )
    (net (code "19") (name "/PD2-RX1") (class "Default")
      (node (ref "JP2") (pin "5") (pinfunction "5_5") (pintype "passive"))
      (node (ref "U6") (pin "27") (pinfunction "PD2_RXD1_INT2_27") (pintype "bidirectional"))
    )
    (net (code "20") (name "/PD3-TX1") (class "Default")
      (node (ref "JP2") (pin "7") (pinfunction "7_7") (pintype "passive"))
      (node (ref "U6") (pin "28") (pinfunction "PD3_TXD1_INT3_28") (pintype "bidirectional"))
    )
    (net (code "21") (name "/PD4") (class "Default")
      (node (ref "JP11") (pin "5") (pinfunction "5_5") (pintype "passive"))
      (node (ref "U6") (pin "29") (pinfunction "PD4_ICP1_29") (pintype "bidirectional"))
    )
    (net (code "22") (name "/PD5") (class "Default")
      (node (ref "JP11") (pin "6") (pinfunction "6_6") (pintype "passive"))
      (node (ref "U6") (pin "30") (pinfunction "PD5_XCK1_30") (pintype "bidirectional"))
    )
    (net (code "23") (name "/PD6") (class "Default")
      (node (ref "JP11") (pin "7") (pinfunction "7_7") (pintype "passive"))
      (node (ref "U6") (pin "31") (pinfunction "PD6_T1_31") (pintype "bidirectional"))
    )
    (net (code "24") (name "/PD7") (class "Default")
      (node (ref "JP11") (pin "8") (pinfunction "8_8") (pintype "passive"))
      (node (ref "U6") (pin "32") (pinfunction "PD7_T0_32") (pintype "bidirectional"))
    )
    (net (code "25") (name "/PE0") (class "Default")
      (node (ref "JP11") (pin "10") (pinfunction "10_10") (pintype "passive"))
      (node (ref "U6") (pin "33") (pinfunction "PE0_/WR_33") (pintype "bidirectional"))
      (node (ref "USBPWR1") (pin "1") (pinfunction "1_1") (pintype "passive"))
    )
    (net (code "26") (name "/PE1") (class "Default")
      (node (ref "JP11") (pin "11") (pinfunction "11_11") (pintype "passive"))
      (node (ref "U6") (pin "34") (pinfunction "PE1_/RD_34") (pintype "bidirectional"))
    )
    (net (code "27") (name "/PE5") (class "Default")
      (node (ref "JP2") (pin "3") (pinfunction "3_3") (pintype "passive"))
      (node (ref "U6") (pin "19") (pinfunction "PE5_INT5_TOSC2_19") (pintype "bidirectional"))
    )
    (net (code "28") (name "/SCL") (class "Default")
      (node (ref "JP7") (pin "1") (pinfunction "1_1") (pintype "passive"))
      (node (ref "R5") (pin "1") (pinfunction "1_1") (pintype "passive"))
      (node (ref "U10") (pin "2") (pinfunction "SCL_2") (pintype "input"))
      (node (ref "U6") (pin "25") (pinfunction "PD0_OC0B_SCL_INT0_25") (pintype "bidirectional"))
    )
    (net (code "29") (name "/SCLK") (class "Default")
      (node (ref "JP4") (pin "4") (pinfunction "4_4") (pintype "passive"))
      (node (ref "U6") (pin "11") (pinfunction "PB1_PCINT1_SCLK_11") (pintype "bidirectional"))
      (node (ref "U8") (pin "12") (pinfunction "B2_12") (pintype "bidirectional"))
    )
    (net (code "30") (name "/SDA") (class "Default")
      (node (ref "JP7") (pin "2") (pinfunction "2_2") (pintype "passive"))
      (node (ref "R15") (pin "1") (pinfunction "1_1") (pintype "passive"))
      (node (ref "U10") (pin "3") (pinfunction "SDA_3") (pintype "bidirectional"))
      (node (ref "U6") (pin "26") (pinfunction "PD1_OC2B_SDA_INT1_26") (pintype "bidirectional"))
    )
    (net (code "31") (name "/SDCD") (class "Default")
      (node (ref "J1") (pin "CD2") (pinfunction "CD2_CD2") (pintype "bidirectional"))
      (node (ref "U6") (pin "17") (pinfunction "PB7_PCINT7_OC0A_OC1C_17") (pintype "bidirectional"))
    )
    (net (code "32") (name "/SDCLK") (class "Default")
      (node (ref "J1") (pin "5") (pinfunction "CLK_5") (pintype "input"))
      (node (ref "U8") (pin "3") (pinfunction "A2_3") (pintype "bidirectional"))
    )
    (net (code "33") (name "/SDCS") (class "Default")
      (node (ref "U6") (pin "10") (pinfunction "PB0_SS_PCINT0_10") (pintype "bidirectional"))
      (node (ref "U8") (pin "10") (pinfunction "B4_10") (pintype "bidirectional"))
    )
    (net (code "34") (name "/SDCSH") (class "Default")
      (node (ref "J1") (pin "2") (pinfunction "DAT3/CS_2") (pintype "bidirectional"))
      (node (ref "U8") (pin "5") (pinfunction "A4_5") (pintype "bidirectional"))
    )
    (net (code "35") (name "/SDDI") (class "Default")
      (node (ref "J1") (pin "3") (pinfunction "CMD/DI_3") (pintype "input"))
      (node (ref "U8") (pin "4") (pinfunction "A3_4") (pintype "bidirectional"))
    )
    (net (code "36") (name "/SDDO") (class "Default")
      (node (ref "J1") (pin "7") (pinfunction "DAT0/DO_7") (pintype "bidirectional"))
      (node (ref "U8") (pin "2") (pinfunction "A1_2") (pintype "bidirectional"))
    )
    (net (code "37") (name "/TCK") (class "Default")
      (node (ref "JP2") (pin "6") (pinfunction "6_6") (pintype "passive"))
      (node (ref "U6") (pin "57") (pinfunction "PF4_ADC4_TCK_57") (pintype "bidirectional"))
    )
    (net (code "38") (name "/TDI") (class "Default")
      (node (ref "JP2") (pin "12") (pinfunction "12_12") (pintype "passive"))
      (node (ref "U6") (pin "54") (pinfunction "PF7_ADC7_TDI_54") (pintype "bidirectional"))
    )
    (net (code "39") (name "/TDO") (class "Default")
      (node (ref "JP2") (pin "10") (pinfunction "10_10") (pintype "passive"))
      (node (ref "U6") (pin "55") (pinfunction "PF6_ADC6_TDO_55") (pintype "bidirectional"))
    )
    (net (code "40") (name "/TMS") (class "Default")
      (node (ref "JP2") (pin "8") (pinfunction "8_8") (pintype "passive"))
      (node (ref "U6") (pin "56") (pinfunction "PF5_ADC5_TMS_56") (pintype "bidirectional"))
    )
    (net (code "41") (name "/VBUS") (class "Default")
      (node (ref "C14") (pin "1") (pinfunction "1_1") (pintype "passive"))
      (node (ref "U$12") (pin "+") (pinfunction "VBUS_+") (pintype "bidirectional"))
      (node (ref "U6") (pin "3") (pinfunction "UVCC_3") (pintype "power_in"))
      (node (ref "U6") (pin "8") (pinfunction "VBUS_8") (pintype "bidirectional"))
      (node (ref "U9") (pin "5") (pinfunction "VCC_5") (pintype "power_in"))
      (node (ref "USBPWR") (pin "1") (pinfunction "1_1") (pintype "passive"))
    )
    (net (code "42") (name "/VREF_E") (class "Default")
      (node (ref "C41") (pin "1") (pinfunction "1_1") (pintype "passive"))
      (node (ref "U10") (pin "6") (pinfunction "VO_A_6") (pintype "output"))
      (node (ref "U5") (pin "12") (pinfunction "REF_12") (pintype "input"))
    )
    (net (code "43") (name "/VREF_X") (class "Default")
      (node (ref "C39") (pin "1") (pinfunction "1_1") (pintype "passive"))
      (node (ref "U10") (pin "9") (pinfunction "VO_D_9") (pintype "output"))
      (node (ref "U2") (pin "12") (pinfunction "REF_12") (pintype "input"))
    )
    (net (code "44") (name "/VREF_Y") (class "Default")
      (node (ref "C38") (pin "1") (pinfunction "1_1") (pintype "passive"))
      (node (ref "U10") (pin "8") (pinfunction "VO_C_8") (pintype "output"))
      (node (ref "U3") (pin "12") (pinfunction "REF_12") (pintype "input"))
    )
    (net (code "45") (name "/VREF_Z") (class "Default")
      (node (ref "C40") (pin "1") (pinfunction "1_1") (pintype "passive"))
      (node (ref "U10") (pin "7") (pinfunction "VO_B_7") (pintype "output"))
      (node (ref "U4") (pin "12") (pinfunction "REF_12") (pintype "input"))
    )
    (net (code "46") (name "/X-DIR") (class "Default")
      (node (ref "U2") (pin "14") (pinfunction "DIR_14") (pintype "input"))
      (node (ref "U6") (pin "50") (pinfunction "PA1_AD1_50") (pintype "bidirectional"))
    )
    (net (code "47") (name "/X-STEP") (class "Default")
      (node (ref "U2") (pin "11") (pinfunction "STEP_11") (pintype "input"))
      (node (ref "U6") (pin "51") (pinfunction "PA0_AD0_51") (pintype "bidirectional"))
    )
    (net (code "48") (name "/X-STOP") (class "Default")
      (node (ref "FB17") (pin "P$1") (pinfunction "1_P$1") (pintype "passive"))
      (node (ref "U6") (pin "9") (pinfunction "PE3_IUID_9") (pintype "bidirectional"))
    )
    (net (code "49") (name "/XTAL1") (class "Default")
      (node (ref "C44") (pin "2") (pinfunction "2_2") (pintype "passive"))
      (node (ref "U6") (pin "24") (pinfunction "XTAL1_24") (pintype "passive"))
      (node (ref "X1") (pin "P$1") (pinfunction "1_P$1") (pintype "passive"))
    )
    (net (code "50") (name "/XTAL2") (class "Default")
      (node (ref "C43") (pin "2") (pinfunction "2_2") (pintype "passive"))
      (node (ref "U6") (pin "23") (pinfunction "XTAL2_23") (pintype "passive"))
      (node (ref "X1") (pin "P$2") (pinfunction "2_P$2") (pintype "passive"))
    )
    (net (code "51") (name "/Y-DIR") (class "Default")
      (node (ref "U3") (pin "14") (pinfunction "DIR_14") (pintype "input"))
      (node (ref "U6") (pin "48") (pinfunction "PA3_AD3_48") (pintype "bidirectional"))
    )
    (net (code "52") (name "/Y-STEP") (class "Default")
      (node (ref "U3") (pin "11") (pinfunction "STEP_11") (pintype "input"))
      (node (ref "U6") (pin "49") (pinfunction "PA2_AD2_49") (pintype "bidirectional"))
    )
    (net (code "53") (name "/Y-STOP") (class "Default")
      (node (ref "FB18") (pin "P$1") (pinfunction "1_P$1") (pintype "passive"))
      (node (ref "U6") (pin "14") (pinfunction "PB4_PCINT4_OC2A_14") (pintype "bidirectional"))
      (node (ref "USBPWR1") (pin "2") (pinfunction "2_2") (pintype "passive"))
      (node (ref "USBPWR2") (pin "1") (pinfunction "1_1") (pintype "passive"))
      (node (ref "USBPWR2") (pin "2") (pinfunction "2_2") (pintype "passive"))
    )
    (net (code "54") (name "/Z-DIR") (class "Default")
      (node (ref "U4") (pin "14") (pinfunction "DIR_14") (pintype "input"))
      (node (ref "U6") (pin "46") (pinfunction "PA5_AD5_46") (pintype "bidirectional"))
    )
    (net (code "55") (name "/Z-STEP") (class "Default")
      (node (ref "U4") (pin "11") (pinfunction "STEP_11") (pintype "input"))
      (node (ref "U6") (pin "47") (pinfunction "PA4_AD4_47") (pintype "bidirectional"))
    )
    (net (code "56") (name "/Z-STOP") (class "Default")
      (node (ref "FB19") (pin "P$1") (pinfunction "1_P$1") (pintype "passive"))
      (node (ref "U6") (pin "18") (pinfunction "PE4_INT4_TOSC1_18") (pintype "bidirectional"))
    )
    (net (code "57") (name "/~{E-ENABLE}") (class "Default")
      (node (ref "R33") (pin "2") (pinfunction "2_2") (pintype "passive"))
      (node (ref "U5") (pin "23") (pinfunction "~{ENABLE}_23") (pintype "input"))
      (node (ref "U6") (pin "38") (pinfunction "PC3_A11_T3_38") (pintype "bidirectional"))
    )
    (net (code "58") (name "/~{HOTBED}") (class "Default")
      (node (ref "R11") (pin "1") (pinfunction "1_1") (pintype "passive"))
      (node (ref "R35") (pin "1") (pinfunction "1_1") (pintype "passive"))
      (node (ref "U6") (pin "39") (pinfunction "PC4_A12_OC3C_39") (pintype "bidirectional"))
    )
    (net (code "59") (name "/~{HOTEND}") (class "Default")
      (node (ref "R36") (pin "1") (pinfunction "1_1") (pintype "passive"))
      (node (ref "R6") (pin "1") (pinfunction "1_1") (pintype "passive"))
      (node (ref "U6") (pin "40") (pinfunction "PC5_A13_OC3B_40") (pintype "bidirectional"))
    )
    (net (code "60") (name "/~{PWM-FAN}") (class "Default")
      (node (ref "Q3") (pin "1") (pinfunction "G_1") (pintype "passive"))
      (node (ref "R14") (pin "1") (pinfunction "1_1") (pintype "passive"))
      (node (ref "U6") (pin "41") (pinfunction "PC6_A14_OC3A_41") (pintype "bidirectional"))
    )
    (net (code "61") (name "/~{RESET}") (class "Default")
      (node (ref "JP4") (pin "2") (pinfunction "2_2") (pintype "passive"))
      (node (ref "R12") (pin "1") (pinfunction "1_1") (pintype "passive"))
      (node (ref "S1") (pin "A2") (pinfunction "1_A2") (pintype "passive"))
      (node (ref "U6") (pin "20") (pinfunction "/RESET_20") (pintype "bidirectional"))
    )
    (net (code "62") (name "/~{X-ENABLE}") (class "Default")
      (node (ref "R3") (pin "2") (pinfunction "2_2") (pintype "passive"))
      (node (ref "U2") (pin "23") (pinfunction "~{ENABLE}_23") (pintype "input"))
      (node (ref "U6") (pin "2") (pinfunction "PE7_INT7_AIN1_UVCON_2") (pintype "bidirectional"))
    )
    (net (code "63") (name "/~{Y-ENABLE}") (class "Default")
      (node (ref "R21") (pin "2") (pinfunction "2_2") (pintype "passive"))
      (node (ref "U3") (pin "23") (pinfunction "~{ENABLE}_23") (pintype "input"))
      (node (ref "U6") (pin "1") (pinfunction "PE6_INT6_AIN0_1") (pintype "bidirectional"))
    )
    (net (code "64") (name "/~{Z-ENABLE}") (class "Default")
      (node (ref "R27") (pin "2") (pinfunction "2_2") (pintype "passive"))
      (node (ref "U4") (pin "23") (pinfunction "~{ENABLE}_23") (pintype "input"))
      (node (ref "U6") (pin "42") (pinfunction "PC7_A15_IC3_CLK0_42") (pintype "bidirectional"))
    )
    (net (code "65") (name "12V") (class "Default")
      (node (ref "C12") (pin "1") (pinfunction "1_1") (pintype "passive"))
      (node (ref "C16") (pin "+") (pinfunction "+_+") (pintype "passive"))
      (node (ref "C18") (pin "+") (pinfunction "+_+") (pintype "passive"))
      (node (ref "C21") (pin "1") (pinfunction "1_1") (pintype "passive"))
      (node (ref "C23") (pin "+") (pinfunction "+_+") (pintype "passive"))
      (node (ref "C26") (pin "1") (pinfunction "1_1") (pintype "passive"))
      (node (ref "C28") (pin "1") (pinfunction "1_1") (pintype "passive"))
      (node (ref "C31") (pin "1") (pinfunction "1_1") (pintype "passive"))
      (node (ref "C33") (pin "1") (pinfunction "1_1") (pintype "passive"))
      (node (ref "C35") (pin "1") (pinfunction "1_1") (pintype "passive"))
      (node (ref "C37") (pin "1") (pinfunction "1_1") (pintype "passive"))
      (node (ref "C4") (pin "1") (pinfunction "1_1") (pintype "passive"))
      (node (ref "C6") (pin "+") (pinfunction "+_+") (pintype "passive"))
      (node (ref "C7") (pin "+") (pinfunction "+_+") (pintype "passive"))
      (node (ref "J2") (pin "P$1") (pinfunction "S_P$1") (pintype "passive"))
      (node (ref "JP17") (pin "1") (pinfunction "1_1") (pintype "passive"))
      (node (ref "JP6") (pin "P$1") (pinfunction "S_P$1") (pintype "passive"))
      (node (ref "R39") (pin "1") (pinfunction "1_1") (pintype "passive"))
      (node (ref "R40") (pin "1") (pinfunction "1_1") (pintype "passive"))
      (node (ref "U$8") (pin "P$4") (pinfunction "P$4_P$4") (pintype "bidirectional"))
      (node (ref "U1") (pin "4") (pinfunction "~{SHDN}_4") (pintype "input"))
      (node (ref "U1") (pin "5") (pinfunction "VIN_5") (pintype "power_in"))
      (node (ref "U2") (pin "16") (pinfunction "VBB1_16") (pintype "power_in"))
      (node (ref "U2") (pin "21") (pinfunction "VBB2_21") (pintype "power_in"))
      (node (ref "U3") (pin "16") (pinfunction "VBB1_16") (pintype "power_in"))
      (node (ref "U3") (pin "21") (pinfunction "VBB2_21") (pintype "power_in"))
      (node (ref "U4") (pin "16") (pinfunction "VBB1_16") (pintype "power_in"))
      (node (ref "U4") (pin "21") (pinfunction "VBB2_21") (pintype "power_in"))
      (node (ref "U5") (pin "16") (pinfunction "VBB1_16") (pintype "power_in"))
      (node (ref "U5") (pin "21") (pinfunction "VBB2_21") (pintype "power_in"))
    )
    (net (code "66") (name "GND") (class "Default")
      (node (ref "C1") (pin "2") (pinfunction "2_2") (pintype "passive"))
      (node (ref "C10") (pin "1") (pinfunction "1_1") (pintype "passive"))
      (node (ref "C11") (pin "1") (pinfunction "1_1") (pintype "passive"))
      (node (ref "C12") (pin "2") (pinfunction "2_2") (pintype "passive"))
      (node (ref "C13") (pin "1") (pinfunction "1_1") (pintype "passive"))
      (node (ref "C14") (pin "2") (pinfunction "2_2") (pintype "passive"))
      (node (ref "C15") (pin "1") (pinfunction "1_1") (pintype "passive"))
      (node (ref "C16") (pin "-") (pinfunction "-_-") (pintype "passive"))
      (node (ref "C18") (pin "-") (pinfunction "-_-") (pintype "passive"))
      (node (ref "C19") (pin "1") (pinfunction "1_1") (pintype "passive"))
      (node (ref "C20") (pin "1") (pinfunction "1_1") (pintype "passive"))
      (node (ref "C23") (pin "-") (pinfunction "-_-") (pintype "passive"))
      (node (ref "C24") (pin "1") (pinfunction "1_1") (pintype "passive"))
      (node (ref "C25") (pin "1") (pinfunction "1_1") (pintype "passive"))
      (node (ref "C28") (pin "2") (pinfunction "2_2") (pintype "passive"))
      (node (ref "C29") (pin "1") (pinfunction "1_1") (pintype "passive"))
      (node (ref "C3") (pin "2") (pinfunction "2_2") (pintype "passive"))
      (node (ref "C30") (pin "1") (pinfunction "1_1") (pintype "passive"))
      (node (ref "C32") (pin "2") (pinfunction "2_2") (pintype "passive"))
      (node (ref "C33") (pin "2") (pinfunction "2_2") (pintype "passive"))
      (node (ref "C34") (pin "1") (pinfunction "1_1") (pintype "passive"))
      (node (ref "C35") (pin "2") (pinfunction "2_2") (pintype "passive"))
      (node (ref "C36") (pin "1") (pinfunction "1_1") (pintype "passive"))
      (node (ref "C37") (pin "2") (pinfunction "2_2") (pintype "passive"))
      (node (ref "C38") (pin "2") (pinfunction "2_2") (pintype "passive"))
      (node (ref "C39") (pin "2") (pinfunction "2_2") (pintype "passive"))
      (node (ref "C40") (pin "2") (pinfunction "2_2") (pintype "passive"))
      (node (ref "C41") (pin "2") (pinfunction "2_2") (pintype "passive"))
      (node (ref "C42") (pin "1") (pinfunction "1_1") (pintype "passive"))
      (node (ref "C43") (pin "1") (pinfunction "1_1") (pintype "passive"))
      (node (ref "C44") (pin "1") (pinfunction "1_1") (pintype "passive"))
      (node (ref "C6") (pin "-") (pinfunction "-_-") (pintype "passive"))
      (node (ref "C7") (pin "-") (pinfunction "-_-") (pintype "passive"))
      (node (ref "C8") (pin "1") (pinfunction "1_1") (pintype "passive"))
      (node (ref "C9") (pin "1") (pinfunction "1_1") (pintype "passive"))
      (node (ref "D1") (pin "A") (pinfunction "A_A") (pintype "passive"))
      (node (ref "D2") (pin "A") (pinfunction "A_A") (pintype "passive"))
      (node (ref "J1") (pin "6") (pinfunction "GND_6") (pintype "power_in"))
      (node (ref "J1") (pin "C1") (pinfunction "SHEILD_C1") (pintype "bidirectional"))
      (node (ref "J1") (pin "C2") (pinfunction "SHIELD_C2") (pintype "bidirectional"))
      (node (ref "J1") (pin "C3") (pinfunction "SHIELD_C3") (pintype "bidirectional"))
      (node (ref "J1") (pin "C4") (pinfunction "SHIELD_C4") (pintype "bidirectional"))
      (node (ref "J1") (pin "CD1") (pinfunction "CD1_CD1") (pintype "bidirectional"))
      (node (ref "JP10") (pin "3") (pinfunction "3_3") (pintype "passive"))
      (node (ref "JP11") (pin "1") (pinfunction "1_1") (pintype "passive"))
      (node (ref "JP12") (pin "3") (pinfunction "3_3") (pintype "passive"))
      (node (ref "JP13") (pin "2") (pinfunction "2_2") (pintype "passive"))
      (node (ref "JP14") (pin "1") (pinfunction "1_1") (pintype "passive"))
      (node (ref "JP15") (pin "2") (pinfunction "2_2") (pintype "passive"))
      (node (ref "JP16") (pin "2") (pinfunction "2_2") (pintype "passive"))
      (node (ref "JP18") (pin "2") (pinfunction "2_2") (pintype "passive"))
      (node (ref "JP2") (pin "14") (pinfunction "14_14") (pintype "passive"))
      (node (ref "JP4") (pin "1") (pinfunction "1_1") (pintype "passive"))
      (node (ref "JP7") (pin "3") (pinfunction "3_3") (pintype "passive"))
      (node (ref "JP8") (pin "3") (pinfunction "3_3") (pintype "passive"))
      (node (ref "LED1") (pin "C") (pinfunction "C_C") (pintype "passive"))
      (node (ref "Q1") (pin "3") (pinfunction "S_3") (pintype "passive"))
      (node (ref "Q2") (pin "3") (pinfunction "S_3") (pintype "passive"))
      (node (ref "Q3") (pin "2") (pinfunction "S_2") (pintype "passive"))
      (node (ref "R14") (pin "2") (pinfunction "2_2") (pintype "passive"))
      (node (ref "R16") (pin "2") (pinfunction "2_2") (pintype "passive"))
      (node (ref "R17") (pin "2") (pinfunction "2_2") (pintype "passive"))
      (node (ref "R18") (pin "2") (pinfunction "2_2") (pintype "passive"))
      (node (ref "R19") (pin "2") (pinfunction "2_2") (pintype "passive"))
      (node (ref "R2") (pin "2") (pinfunction "2_2") (pintype "passive"))
      (node (ref "R20") (pin "2") (pinfunction "2_2") (pintype "passive"))
      (node (ref "R24") (pin "2") (pinfunction "2_2") (pintype "passive"))
      (node (ref "R25") (pin "2") (pinfunction "2_2") (pintype "passive"))
      (node (ref "R26") (pin "2") (pinfunction "2_2") (pintype "passive"))
      (node (ref "R30") (pin "2") (pinfunction "2_2") (pintype "passive"))
      (node (ref "R31") (pin "2") (pinfunction "2_2") (pintype "passive"))
      (node (ref "R32") (pin "2") (pinfunction "2_2") (pintype "passive"))
      (node (ref "R35") (pin "2") (pinfunction "2_2") (pintype "passive"))
      (node (ref "R38") (pin "2") (pinfunction "2_2") (pintype "passive"))
      (node (ref "R6") (pin "2") (pinfunction "2_2") (pintype "passive"))
      (node (ref "S1") (pin "B2") (pinfunction "2_B2") (pintype "passive"))
      (node (ref "U$12") (pin "-") (pinfunction "GND_-") (pintype "bidirectional"))
      (node (ref "U$12") (pin "P$5") (pinfunction "SHIELD_P$5") (pintype "bidirectional"))
      (node (ref "U$12") (pin "P$6") (pinfunction "SHIELD_P$6") (pintype "bidirectional"))
      (node (ref "U$8") (pin "P$3") (pinfunction "P$3_P$3") (pintype "bidirectional"))
      (node (ref "U1") (pin "2") (pinfunction "GND_2") (pintype "power_in"))
      (node (ref "U10") (pin "10") (pinfunction "VSS_10") (pintype "power_in"))
      (node (ref "U2") (pin "13") (pinfunction "GND1_13") (pintype "power_in"))
      (node (ref "U2") (pin "24") (pinfunction "GND2_24") (pintype "power_in"))
      (node (ref "U2") (pin "PAD") (pinfunction "PAD_PAD") (pintype "power_in"))
      (node (ref "U3") (pin "13") (pinfunction "GND1_13") (pintype "power_in"))
      (node (ref "U3") (pin "24") (pinfunction "GND2_24") (pintype "power_in"))
      (node (ref "U3") (pin "PAD") (pinfunction "PAD_PAD") (pintype "power_in"))
      (node (ref "U4") (pin "13") (pinfunction "GND1_13") (pintype "power_in"))
      (node (ref "U4") (pin "24") (pinfunction "GND2_24") (pintype "power_in"))
      (node (ref "U4") (pin "PAD") (pinfunction "PAD_PAD") (pintype "power_in"))
      (node (ref "U5") (pin "13") (pinfunction "GND1_13") (pintype "power_in"))
      (node (ref "U5") (pin "24") (pinfunction "GND2_24") (pintype "power_in"))
      (node (ref "U5") (pin "PAD") (pinfunction "PAD_PAD") (pintype "power_in"))
      (node (ref "U6") (pin "22") (pinfunction "GND_22") (pintype "power_in"))
      (node (ref "U6") (pin "53") (pinfunction "GND_53") (pintype "power_in"))
      (node (ref "U6") (pin "6") (pinfunction "UGND_6") (pintype "power_in"))
      (node (ref "U6") (pin "63") (pinfunction "AGND_63") (pintype "power_in"))
      (node (ref "U7") (pin "3") (pinfunction "GND_3") (pintype "power_in"))
      (node (ref "U8") (pin "7") (pinfunction "GND_7") (pintype "power_in"))
      (node (ref "U9") (pin "2") (pinfunction "GND_2") (pintype "power_in"))
    )
    (net (code "67") (name "Net-(FB1-1)") (class "Default")
      (node (ref "FB1") (pin "P$1") (pinfunction "1_P$1") (pintype "passive"))
      (node (ref "U2") (pin "22") (pinfunction "OUT2B_22") (pintype "output"))
    )
    (net (code "68") (name "Net-(FB1-2)") (class "Default")
      (node (ref "FB1") (pin "P$2") (pinfunction "2_P$2") (pintype "passive"))
      (node (ref "JP9") (pin "1") (pinfunction "1_1") (pintype "passive"))
    )
    (net (code "69") (name "Net-(FB2-1)") (class "Default")
      (node (ref "FB2") (pin "P$1") (pinfunction "1_P$1") (pintype "passive"))
      (node (ref "U2") (pin "19") (pinfunction "OUT2A_19") (pintype "output"))
    )
    (net (code "70") (name "Net-(FB2-2)") (class "Default")
      (node (ref "FB2") (pin "P$2") (pinfunction "2_P$2") (pintype "passive"))
      (node (ref "JP9") (pin "2") (pinfunction "2_2") (pintype "passive"))
    )
    (net (code "71") (name "Net-(FB3-1)") (class "Default")
      (node (ref "FB3") (pin "P$1") (pinfunction "1_P$1") (pintype "passive"))
      (node (ref "U2") (pin "18") (pinfunction "OUT1A_18") (pintype "output"))
    )
    (net (code "72") (name "Net-(FB3-2)") (class "Default")
      (node (ref "FB3") (pin "P$2") (pinfunction "2_P$2") (pintype "passive"))
      (node (ref "JP9") (pin "3") (pinfunction "3_3") (pintype "passive"))
    )
    (net (code "73") (name "Net-(FB4-1)") (class "Default")
      (node (ref "FB4") (pin "P$1") (pinfunction "1_P$1") (pintype "passive"))
      (node (ref "U2") (pin "15") (pinfunction "OUT1B_15") (pintype "output"))
    )
    (net (code "74") (name "Net-(FB4-2)") (class "Default")
      (node (ref "FB4") (pin "P$2") (pinfunction "2_P$2") (pintype "passive"))
      (node (ref "JP9") (pin "4") (pinfunction "4_4") (pintype "passive"))
    )
    (net (code "75") (name "Net-(FB5-1)") (class "Default")
      (node (ref "FB5") (pin "P$1") (pinfunction "1_P$1") (pintype "passive"))
      (node (ref "U3") (pin "22") (pinfunction "OUT2B_22") (pintype "output"))
    )
    (net (code "76") (name "Net-(FB5-2)") (class "Default")
      (node (ref "FB5") (pin "P$2") (pinfunction "2_P$2") (pintype "passive"))
      (node (ref "JP1") (pin "1") (pinfunction "1_1") (pintype "passive"))
    )
    (net (code "77") (name "Net-(FB6-1)") (class "Default")
      (node (ref "FB6") (pin "P$1") (pinfunction "1_P$1") (pintype "passive"))
      (node (ref "U3") (pin "19") (pinfunction "OUT2A_19") (pintype "output"))
    )
    (net (code "78") (name "Net-(FB6-2)") (class "Default")
      (node (ref "FB6") (pin "P$2") (pinfunction "2_P$2") (pintype "passive"))
      (node (ref "JP1") (pin "2") (pinfunction "2_2") (pintype "passive"))
    )
    (net (code "79") (name "Net-(FB7-1)") (class "Default")
      (node (ref "FB7") (pin "P$1") (pinfunction "1_P$1") (pintype "passive"))
      (node (ref "U3") (pin "18") (pinfunction "OUT1A_18") (pintype "output"))
    )
    (net (code "80") (name "Net-(FB7-2)") (class "Default")
      (node (ref "FB7") (pin "P$2") (pinfunction "2_P$2") (pintype "passive"))
      (node (ref "JP1") (pin "3") (pinfunction "3_3") (pintype "passive"))
    )
    (net (code "81") (name "Net-(FB8-1)") (class "Default")
      (node (ref "FB8") (pin "P$1") (pinfunction "1_P$1") (pintype "passive"))
      (node (ref "U3") (pin "15") (pinfunction "OUT1B_15") (pintype "output"))
    )
    (net (code "82") (name "Net-(FB8-2)") (class "Default")
      (node (ref "FB8") (pin "P$2") (pinfunction "2_P$2") (pintype "passive"))
      (node (ref "JP1") (pin "4") (pinfunction "4_4") (pintype "passive"))
    )
    (net (code "83") (name "Net-(FB9-1)") (class "Default")
      (node (ref "FB9") (pin "P$1") (pinfunction "1_P$1") (pintype "passive"))
      (node (ref "U4") (pin "22") (pinfunction "OUT2B_22") (pintype "output"))
    )
    (net (code "84") (name "Net-(FB9-2)") (class "Default")
      (node (ref "FB9") (pin "P$2") (pinfunction "2_P$2") (pintype "passive"))
      (node (ref "JP3") (pin "1") (pinfunction "1_1") (pintype "passive"))
    )
    (net (code "85") (name "Net-(FB10-1)") (class "Default")
      (node (ref "FB10") (pin "P$1") (pinfunction "1_P$1") (pintype "passive"))
      (node (ref "U4") (pin "19") (pinfunction "OUT2A_19") (pintype "output"))
    )
    (net (code "86") (name "Net-(FB10-2)") (class "Default")
      (node (ref "FB10") (pin "P$2") (pinfunction "2_P$2") (pintype "passive"))
      (node (ref "JP3") (pin "2") (pinfunction "2_2") (pintype "passive"))
    )
    (net (code "87") (name "Net-(FB11-1)") (class "Default")
      (node (ref "FB11") (pin "P$1") (pinfunction "1_P$1") (pintype "passive"))
      (node (ref "U4") (pin "18") (pinfunction "OUT1A_18") (pintype "output"))
    )
    (net (code "88") (name "Net-(FB11-2)") (class "Default")
      (node (ref "FB11") (pin "P$2") (pinfunction "2_P$2") (pintype "passive"))
      (node (ref "JP3") (pin "3") (pinfunction "3_3") (pintype "passive"))
    )
    (net (code "89") (name "Net-(FB12-1)") (class "Default")
      (node (ref "FB12") (pin "P$1") (pinfunction "1_P$1") (pintype "passive"))
      (node (ref "U4") (pin "15") (pinfunction "OUT1B_15") (pintype "output"))
    )
    (net (code "90") (name "Net-(FB12-2)") (class "Default")
      (node (ref "FB12") (pin "P$2") (pinfunction "2_P$2") (pintype "passive"))
      (node (ref "JP3") (pin "4") (pinfunction "4_4") (pintype "passive"))
    )
    (net (code "91") (name "Net-(FB13-1)") (class "Default")
      (node (ref "FB13") (pin "P$1") (pinfunction "1_P$1") (pintype "passive"))
      (node (ref "U5") (pin "22") (pinfunction "OUT2B_22") (pintype "output"))
    )
    (net (code "92") (name "Net-(FB13-2)") (class "Default")
      (node (ref "FB13") (pin "P$2") (pinfunction "2_P$2") (pintype "passive"))
      (node (ref "JP5") (pin "1") (pinfunction "1_1") (pintype "passive"))
    )
    (net (code "93") (name "Net-(FB14-1)") (class "Default")
      (node (ref "FB14") (pin "P$1") (pinfunction "1_P$1") (pintype "passive"))
      (node (ref "U5") (pin "19") (pinfunction "OUT2A_19") (pintype "output"))
    )
    (net (code "94") (name "Net-(FB14-2)") (class "Default")
      (node (ref "FB14") (pin "P$2") (pinfunction "2_P$2") (pintype "passive"))
      (node (ref "JP5") (pin "2") (pinfunction "2_2") (pintype "passive"))
    )
    (net (code "95") (name "Net-(FB15-1)") (class "Default")
      (node (ref "FB15") (pin "P$1") (pinfunction "1_P$1") (pintype "passive"))
      (node (ref "U5") (pin "18") (pinfunction "OUT1A_18") (pintype "output"))
    )
    (net (code "96") (name "Net-(FB15-2)") (class "Default")
      (node (ref "FB15") (pin "P$2") (pinfunction "2_P$2") (pintype "passive"))
      (node (ref "JP5") (pin "3") (pinfunction "3_3") (pintype "passive"))
    )
    (net (code "97") (name "Net-(FB16-1)") (class "Default")
      (node (ref "FB16") (pin "P$1") (pinfunction "1_P$1") (pintype "passive"))
      (node (ref "U5") (pin "15") (pinfunction "OUT1B_15") (pintype "output"))
    )
    (net (code "98") (name "Net-(FB16-2)") (class "Default")
      (node (ref "FB16") (pin "P$2") (pinfunction "2_P$2") (pintype "passive"))
      (node (ref "JP5") (pin "4") (pinfunction "4_4") (pintype "passive"))
    )
    (net (code "99") (name "Net-(FB17-2)") (class "Default")
      (node (ref "FB17") (pin "P$2") (pinfunction "2_P$2") (pintype "passive"))
      (node (ref "JP12") (pin "1") (pinfunction "1_1") (pintype "passive"))
    )
    (net (code "100") (name "Net-(FB18-2)") (class "Default")
      (node (ref "FB18") (pin "P$2") (pinfunction "2_P$2") (pintype "passive"))
      (node (ref "JP8") (pin "1") (pinfunction "1_1") (pintype "passive"))
    )
    (net (code "101") (name "Net-(FB19-2)") (class "Default")
      (node (ref "FB19") (pin "P$2") (pinfunction "2_P$2") (pintype "passive"))
      (node (ref "JP10") (pin "1") (pinfunction "1_1") (pintype "passive"))
    )
    (net (code "102") (name "Net-(FB20-1)") (class "Default")
      (node (ref "FB20") (pin "P$1") (pinfunction "1_P$1") (pintype "passive"))
      (node (ref "R39") (pin "2") (pinfunction "2_2") (pintype "passive"))
    )
    (net (code "103") (name "Net-(FB20-2)") (class "Default")
      (node (ref "FB20") (pin "P$2") (pinfunction "2_P$2") (pintype "passive"))
      (node (ref "JP13") (pin "1") (pinfunction "1_1") (pintype "passive"))
    )
    (net (code "104") (name "Net-(FB21-1)") (class "Default")
      (node (ref "FB21") (pin "P$1") (pinfunction "1_P$1") (pintype "passive"))
      (node (ref "R40") (pin "2") (pinfunction "2_2") (pintype "passive"))
    )
    (net (code "105") (name "Net-(FB21-2)") (class "Default")
      (node (ref "FB21") (pin "P$2") (pinfunction "2_P$2") (pintype "passive"))
      (node (ref "JP18") (pin "1") (pinfunction "1_1") (pintype "passive"))
    )
    (net (code "106") (name "Net-(J2B-S)") (class "Default")
      (node (ref "J2") (pin "P$2") (pinfunction "S_P$2") (pintype "passive"))
      (node (ref "Q2") (pin "2") (pinfunction "D_2") (pintype "passive"))
    )
    (net (code "107") (name "Net-(J3A-S)") (class "Default")
      (node (ref "J3") (pin "P$1") (pinfunction "S_P$1") (pintype "passive"))
      (node (ref "U$8") (pin "P$1") (pinfunction "P$1_P$1") (pintype "bidirectional"))
    )
    (net (code "108") (name "Net-(J3B-S)") (class "Default")
      (node (ref "J3") (pin "P$2") (pinfunction "S_P$2") (pintype "passive"))
      (node (ref "U$8") (pin "P$2") (pinfunction "P$2_P$2") (pintype "bidirectional"))
    )
    (net (code "109") (name "Net-(JP6B-S)") (class "Default")
      (node (ref "JP6") (pin "P$2") (pinfunction "S_P$2") (pintype "passive"))
      (node (ref "Q1") (pin "2") (pinfunction "D_2") (pintype "passive"))
    )
    (net (code "110") (name "Net-(JP17-Pad2)") (class "Default")
      (node (ref "JP17") (pin "2") (pinfunction "2_2") (pintype "passive"))
      (node (ref "R41") (pin "2") (pinfunction "2_2") (pintype "passive"))
    )
    (net (code "111") (name "Net-(L1-1)") (class "Default")
      (node (ref "C2") (pin "1") (pinfunction "1_1") (pintype "passive"))
      (node (ref "D1") (pin "C") (pinfunction "C_C") (pintype "passive"))
      (node (ref "L1") (pin "P$1") (pinfunction "1_P$1") (pintype "passive"))
      (node (ref "U1") (pin "6") (pinfunction "SW_6") (pintype "passive"))
    )
    (net (code "112") (name "Net-(LED1-PadA)") (class "Default")
      (node (ref "LED1") (pin "A") (pinfunction "A_A") (pintype "passive"))
      (node (ref "R1") (pin "1") (pinfunction "1_1") (pintype "passive"))
    )
    (net (code "113") (name "Net-(Q1-G)") (class "Default")
      (node (ref "Q1") (pin "1") (pinfunction "G_1") (pintype "passive"))
      (node (ref "R36") (pin "2") (pinfunction "2_2") (pintype "passive"))
    )
    (net (code "114") (name "Net-(Q2-G)") (class "Default")
      (node (ref "Q2") (pin "1") (pinfunction "G_1") (pintype "passive"))
      (node (ref "R11") (pin "2") (pinfunction "2_2") (pintype "passive"))
    )
    (net (code "115") (name "Net-(Q3-D)") (class "Default")
      (node (ref "D2") (pin "C") (pinfunction "C_C") (pintype "passive"))
      (node (ref "Q3") (pin "3") (pinfunction "D_3") (pintype "passive"))
      (node (ref "R41") (pin "1") (pinfunction "1_1") (pintype "passive"))
    )
    (net (code "116") (name "Net-(U1-CB)") (class "Default")
      (node (ref "C2") (pin "2") (pinfunction "2_2") (pintype "passive"))
      (node (ref "U1") (pin "1") (pinfunction "CB_1") (pintype "passive"))
    )
    (net (code "117") (name "Net-(U1-FB)") (class "Default")
      (node (ref "R37") (pin "2") (pinfunction "2_2") (pintype "passive"))
      (node (ref "R38") (pin "1") (pinfunction "1_1") (pintype "passive"))
      (node (ref "U1") (pin "3") (pinfunction "FB_3") (pintype "passive"))
    )
    (net (code "118") (name "Net-(U2-CP1)") (class "Default")
      (node (ref "C5") (pin "2") (pinfunction "2_2") (pintype "passive"))
      (node (ref "U2") (pin "1") (pinfunction "CP1_1") (pintype "passive"))
    )
    (net (code "119") (name "Net-(U2-CP2)") (class "Default")
      (node (ref "C5") (pin "1") (pinfunction "1_1") (pintype "passive"))
      (node (ref "U2") (pin "2") (pinfunction "CP2_2") (pintype "passive"))
    )
    (net (code "120") (name "Net-(U2-MS1)") (class "Default")
      (node (ref "MS-X") (pin "1") (pinfunction "1_1") (pintype "passive"))
      (node (ref "U2") (pin "5") (pinfunction "MS1_5") (pintype "input"))
    )
    (net (code "121") (name "Net-(U2-MS2)") (class "Default")
      (node (ref "MS-X") (pin "3") (pinfunction "3_3") (pintype "passive"))
      (node (ref "U2") (pin "6") (pinfunction "MS2_6") (pintype "input"))
    )
    (net (code "122") (name "Net-(U2-ROSC)") (class "Default")
      (node (ref "R2") (pin "1") (pinfunction "1_1") (pintype "passive"))
      (node (ref "U2") (pin "8") (pinfunction "ROSC_8") (pintype "passive"))
    )
    (net (code "123") (name "Net-(U2-SENSE1)") (class "Default")
      (node (ref "R17") (pin "1") (pinfunction "1_1") (pintype "passive"))
      (node (ref "U2") (pin "17") (pinfunction "SENSE1_17") (pintype "passive"))
    )
    (net (code "124") (name "Net-(U2-SENSE2)") (class "Default")
      (node (ref "R18") (pin "1") (pinfunction "1_1") (pintype "passive"))
      (node (ref "U2") (pin "20") (pinfunction "SENSE2_20") (pintype "passive"))
    )
    (net (code "125") (name "Net-(U2-VCP)") (class "Default")
      (node (ref "C4") (pin "2") (pinfunction "2_2") (pintype "passive"))
      (node (ref "U2") (pin "3") (pinfunction "VCP_3") (pintype "passive"))
    )
    (net (code "126") (name "Net-(U2-VREG)") (class "Default")
      (node (ref "C8") (pin "2") (pinfunction "2_2") (pintype "passive"))
      (node (ref "U2") (pin "4") (pinfunction "VREG_4") (pintype "passive"))
    )
    (net (code "127") (name "Net-(U2-~{RESET})") (class "Default")
      (node (ref "R4") (pin "2") (pinfunction "2_2") (pintype "passive"))
      (node (ref "U2") (pin "7") (pinfunction "~{RESET}_7") (pintype "input"))
      (node (ref "U2") (pin "9") (pinfunction "~{SLEEP}_9") (pintype "input"))
    )
    (net (code "128") (name "Net-(U3-CP1)") (class "Default")
      (node (ref "C17") (pin "2") (pinfunction "2_2") (pintype "passive"))
      (node (ref "U3") (pin "1") (pinfunction "CP1_1") (pintype "passive"))
    )
    (net (code "129") (name "Net-(U3-CP2)") (class "Default")
      (node (ref "C17") (pin "1") (pinfunction "1_1") (pintype "passive"))
      (node (ref "U3") (pin "2") (pinfunction "CP2_2") (pintype "passive"))
    )
    (net (code "130") (name "Net-(U3-MS1)") (class "Default")
      (node (ref "MS-Y") (pin "1") (pinfunction "1_1") (pintype "passive"))
      (node (ref "U3") (pin "5") (pinfunction "MS1_5") (pintype "input"))
    )
    (net (code "131") (name "Net-(U3-MS2)") (class "Default")
      (node (ref "MS-Y") (pin "3") (pinfunction "3_3") (pintype "passive"))
      (node (ref "U3") (pin "6") (pinfunction "MS2_6") (pintype "input"))
    )
    (net (code "132") (name "Net-(U3-ROSC)") (class "Default")
      (node (ref "R20") (pin "1") (pinfunction "1_1") (pintype "passive"))
      (node (ref "U3") (pin "8") (pinfunction "ROSC_8") (pintype "passive"))
    )
    (net (code "133") (name "Net-(U3-SENSE1)") (class "Default")
      (node (ref "R16") (pin "1") (pinfunction "1_1") (pintype "passive"))
      (node (ref "U3") (pin "17") (pinfunction "SENSE1_17") (pintype "passive"))
    )
    (net (code "134") (name "Net-(U3-SENSE2)") (class "Default")
      (node (ref "R19") (pin "1") (pinfunction "1_1") (pintype "passive"))
      (node (ref "U3") (pin "20") (pinfunction "SENSE2_20") (pintype "passive"))
    )
    (net (code "135") (name "Net-(U3-VCP)") (class "Default")
      (node (ref "C21") (pin "2") (pinfunction "2_2") (pintype "passive"))
      (node (ref "U3") (pin "3") (pinfunction "VCP_3") (pintype "passive"))
    )
    (net (code "136") (name "Net-(U3-VREG)") (class "Default")
      (node (ref "C19") (pin "2") (pinfunction "2_2") (pintype "passive"))
      (node (ref "U3") (pin "4") (pinfunction "VREG_4") (pintype "passive"))
    )
    (net (code "137") (name "Net-(U3-~{RESET})") (class "Default")
      (node (ref "R22") (pin "2") (pinfunction "2_2") (pintype "passive"))
      (node (ref "U3") (pin "7") (pinfunction "~{RESET}_7") (pintype "input"))
      (node (ref "U3") (pin "9") (pinfunction "~{SLEEP}_9") (pintype "input"))
    )
    (net (code "138") (name "Net-(U4-CP1)") (class "Default")
      (node (ref "C22") (pin "2") (pinfunction "2_2") (pintype "passive"))
      (node (ref "U4") (pin "1") (pinfunction "CP1_1") (pintype "passive"))
    )
    (net (code "139") (name "Net-(U4-CP2)") (class "Default")
      (node (ref "C22") (pin "1") (pinfunction "1_1") (pintype "passive"))
      (node (ref "U4") (pin "2") (pinfunction "CP2_2") (pintype "passive"))
    )
    (net (code "140") (name "Net-(U4-MS1)") (class "Default")
      (node (ref "MS-Z") (pin "1") (pinfunction "1_1") (pintype "passive"))
      (node (ref "U4") (pin "5") (pinfunction "MS1_5") (pintype "input"))
    )
    (net (code "141") (name "Net-(U4-MS2)") (class "Default")
      (node (ref "MS-Z") (pin "3") (pinfunction "3_3") (pintype "passive"))
      (node (ref "U4") (pin "6") (pinfunction "MS2_6") (pintype "input"))
    )
    (net (code "142") (name "Net-(U4-ROSC)") (class "Default")
      (node (ref "R26") (pin "1") (pinfunction "1_1") (pintype "passive"))
      (node (ref "U4") (pin "8") (pinfunction "ROSC_8") (pintype "passive"))
    )
    (net (code "143") (name "Net-(U4-SENSE1)") (class "Default")
      (node (ref "R24") (pin "1") (pinfunction "1_1") (pintype "passive"))
      (node (ref "U4") (pin "17") (pinfunction "SENSE1_17") (pintype "passive"))
    )
    (net (code "144") (name "Net-(U4-SENSE2)") (class "Default")
      (node (ref "R25") (pin "1") (pinfunction "1_1") (pintype "passive"))
      (node (ref "U4") (pin "20") (pinfunction "SENSE2_20") (pintype "passive"))
    )
    (net (code "145") (name "Net-(U4-VCP)") (class "Default")
      (node (ref "C26") (pin "2") (pinfunction "2_2") (pintype "passive"))
      (node (ref "U4") (pin "3") (pinfunction "VCP_3") (pintype "passive"))
    )
    (net (code "146") (name "Net-(U4-VREG)") (class "Default")
      (node (ref "C24") (pin "2") (pinfunction "2_2") (pintype "passive"))
      (node (ref "U4") (pin "4") (pinfunction "VREG_4") (pintype "passive"))
    )
    (net (code "147") (name "Net-(U4-~{RESET})") (class "Default")
      (node (ref "R28") (pin "2") (pinfunction "2_2") (pintype "passive"))
      (node (ref "U4") (pin "7") (pinfunction "~{RESET}_7") (pintype "input"))
      (node (ref "U4") (pin "9") (pinfunction "~{SLEEP}_9") (pintype "input"))
    )
    (net (code "148") (name "Net-(U5-CP1)") (class "Default")
      (node (ref "C27") (pin "2") (pinfunction "2_2") (pintype "passive"))
      (node (ref "U5") (pin "1") (pinfunction "CP1_1") (pintype "passive"))
    )
    (net (code "149") (name "Net-(U5-CP2)") (class "Default")
      (node (ref "C27") (pin "1") (pinfunction "1_1") (pintype "passive"))
      (node (ref "U5") (pin "2") (pinfunction "CP2_2") (pintype "passive"))
    )
    (net (code "150") (name "Net-(U5-MS1)") (class "Default")
      (node (ref "MS-E") (pin "1") (pinfunction "1_1") (pintype "passive"))
      (node (ref "U5") (pin "5") (pinfunction "MS1_5") (pintype "input"))
    )
    (net (code "151") (name "Net-(U5-MS2)") (class "Default")
      (node (ref "MS-E") (pin "3") (pinfunction "3_3") (pintype "passive"))
      (node (ref "U5") (pin "6") (pinfunction "MS2_6") (pintype "input"))
    )
    (net (code "152") (name "Net-(U5-ROSC)") (class "Default")
      (node (ref "R32") (pin "1") (pinfunction "1_1") (pintype "passive"))
      (node (ref "U5") (pin "8") (pinfunction "ROSC_8") (pintype "passive"))
    )
    (net (code "153") (name "Net-(U5-SENSE1)") (class "Default")
      (node (ref "R30") (pin "1") (pinfunction "1_1") (pintype "passive"))
      (node (ref "U5") (pin "17") (pinfunction "SENSE1_17") (pintype "passive"))
    )
    (net (code "154") (name "Net-(U5-SENSE2)") (class "Default")
      (node (ref "R31") (pin "1") (pinfunction "1_1") (pintype "passive"))
      (node (ref "U5") (pin "20") (pinfunction "SENSE2_20") (pintype "passive"))
    )
    (net (code "155") (name "Net-(U5-VCP)") (class "Default")
      (node (ref "C31") (pin "2") (pinfunction "2_2") (pintype "passive"))
      (node (ref "U5") (pin "3") (pinfunction "VCP_3") (pintype "passive"))
    )
    (net (code "156") (name "Net-(U5-VREG)") (class "Default")
      (node (ref "C29") (pin "2") (pinfunction "2_2") (pintype "passive"))
      (node (ref "U5") (pin "4") (pinfunction "VREG_4") (pintype "passive"))
    )
    (net (code "157") (name "Net-(U5-~{RESET})") (class "Default")
      (node (ref "R34") (pin "2") (pinfunction "2_2") (pintype "passive"))
      (node (ref "U5") (pin "7") (pinfunction "~{RESET}_7") (pintype "input"))
      (node (ref "U5") (pin "9") (pinfunction "~{SLEEP}_9") (pintype "input"))
    )
    (net (code "158") (name "Net-(U6-AREF)") (class "Default")
      (node (ref "C3") (pin "1") (pinfunction "1_1") (pintype "passive"))
      (node (ref "U6") (pin "62") (pinfunction "AREF_62") (pintype "power_in"))
    )
    (net (code "159") (name "Net-(U6-D+)") (class "Default")
      (node (ref "R8") (pin "2") (pinfunction "2_2") (pintype "passive"))
      (node (ref "U6") (pin "5") (pinfunction "D+_5") (pintype "bidirectional"))
    )
    (net (code "160") (name "Net-(U6-D-)") (class "Default")
      (node (ref "R7") (pin "2") (pinfunction "2_2") (pintype "passive"))
      (node (ref "U6") (pin "4") (pinfunction "D-_4") (pintype "bidirectional"))
    )
    (net (code "161") (name "Net-(U6-UCAP)") (class "Default")
      (node (ref "C11") (pin "2") (pinfunction "2_2") (pintype "passive"))
      (node (ref "U6") (pin "7") (pinfunction "UCAP_7") (pintype "power_in"))
    )
    (net (code "162") (name "unconnected-(J1-DAT1-Pad8)") (class "Default")
      (node (ref "J1") (pin "8") (pinfunction "DAT1_8") (pintype "bidirectional"))
    )
    (net (code "163") (name "unconnected-(J1-DAT2-Pad1)") (class "Default")
      (node (ref "J1") (pin "1") (pinfunction "DAT2_1") (pintype "bidirectional"))
    )
    (net (code "164") (name "unconnected-(JP2-Pad9)") (class "Default")
      (node (ref "JP2") (pin "9") (pinfunction "9_9") (pintype "passive"))
    )
    (net (code "165") (name "unconnected-(JP11-Pad3)") (class "Default")
      (node (ref "JP11") (pin "3") (pinfunction "3_3") (pintype "passive"))
    )
    (net (code "166") (name "unconnected-(JP11-Pad4)") (class "Default")
      (node (ref "JP11") (pin "4") (pinfunction "4_4") (pintype "passive"))
    )
    (net (code "167") (name "unconnected-(JP11-Pad9)") (class "Default")
      (node (ref "JP11") (pin "9") (pinfunction "9_9") (pintype "passive"))
    )
    (net (code "168") (name "unconnected-(U9-IO3-Pad4)") (class "Default")
      (node (ref "U9") (pin "4") (pinfunction "IO3_4") (pintype "bidirectional"))
    )
    (net (code "169") (name "unconnected-(U9-IO4-Pad6)") (class "Default")
      (node (ref "U9") (pin "6") (pinfunction "IO4_6") (pintype "bidirectional"))
    )
    (net (code "170") (name "unconnected-(U10-RDY{slash}~{BSY}-Pad5)") (class "Default")
      (node (ref "U10") (pin "5") (pinfunction "RDY/~{BSY}_5") (pintype "input"))
    )
  )
)
